# boden2021_V35.net
KiCad netlist of a schematic drawn in EAGLE
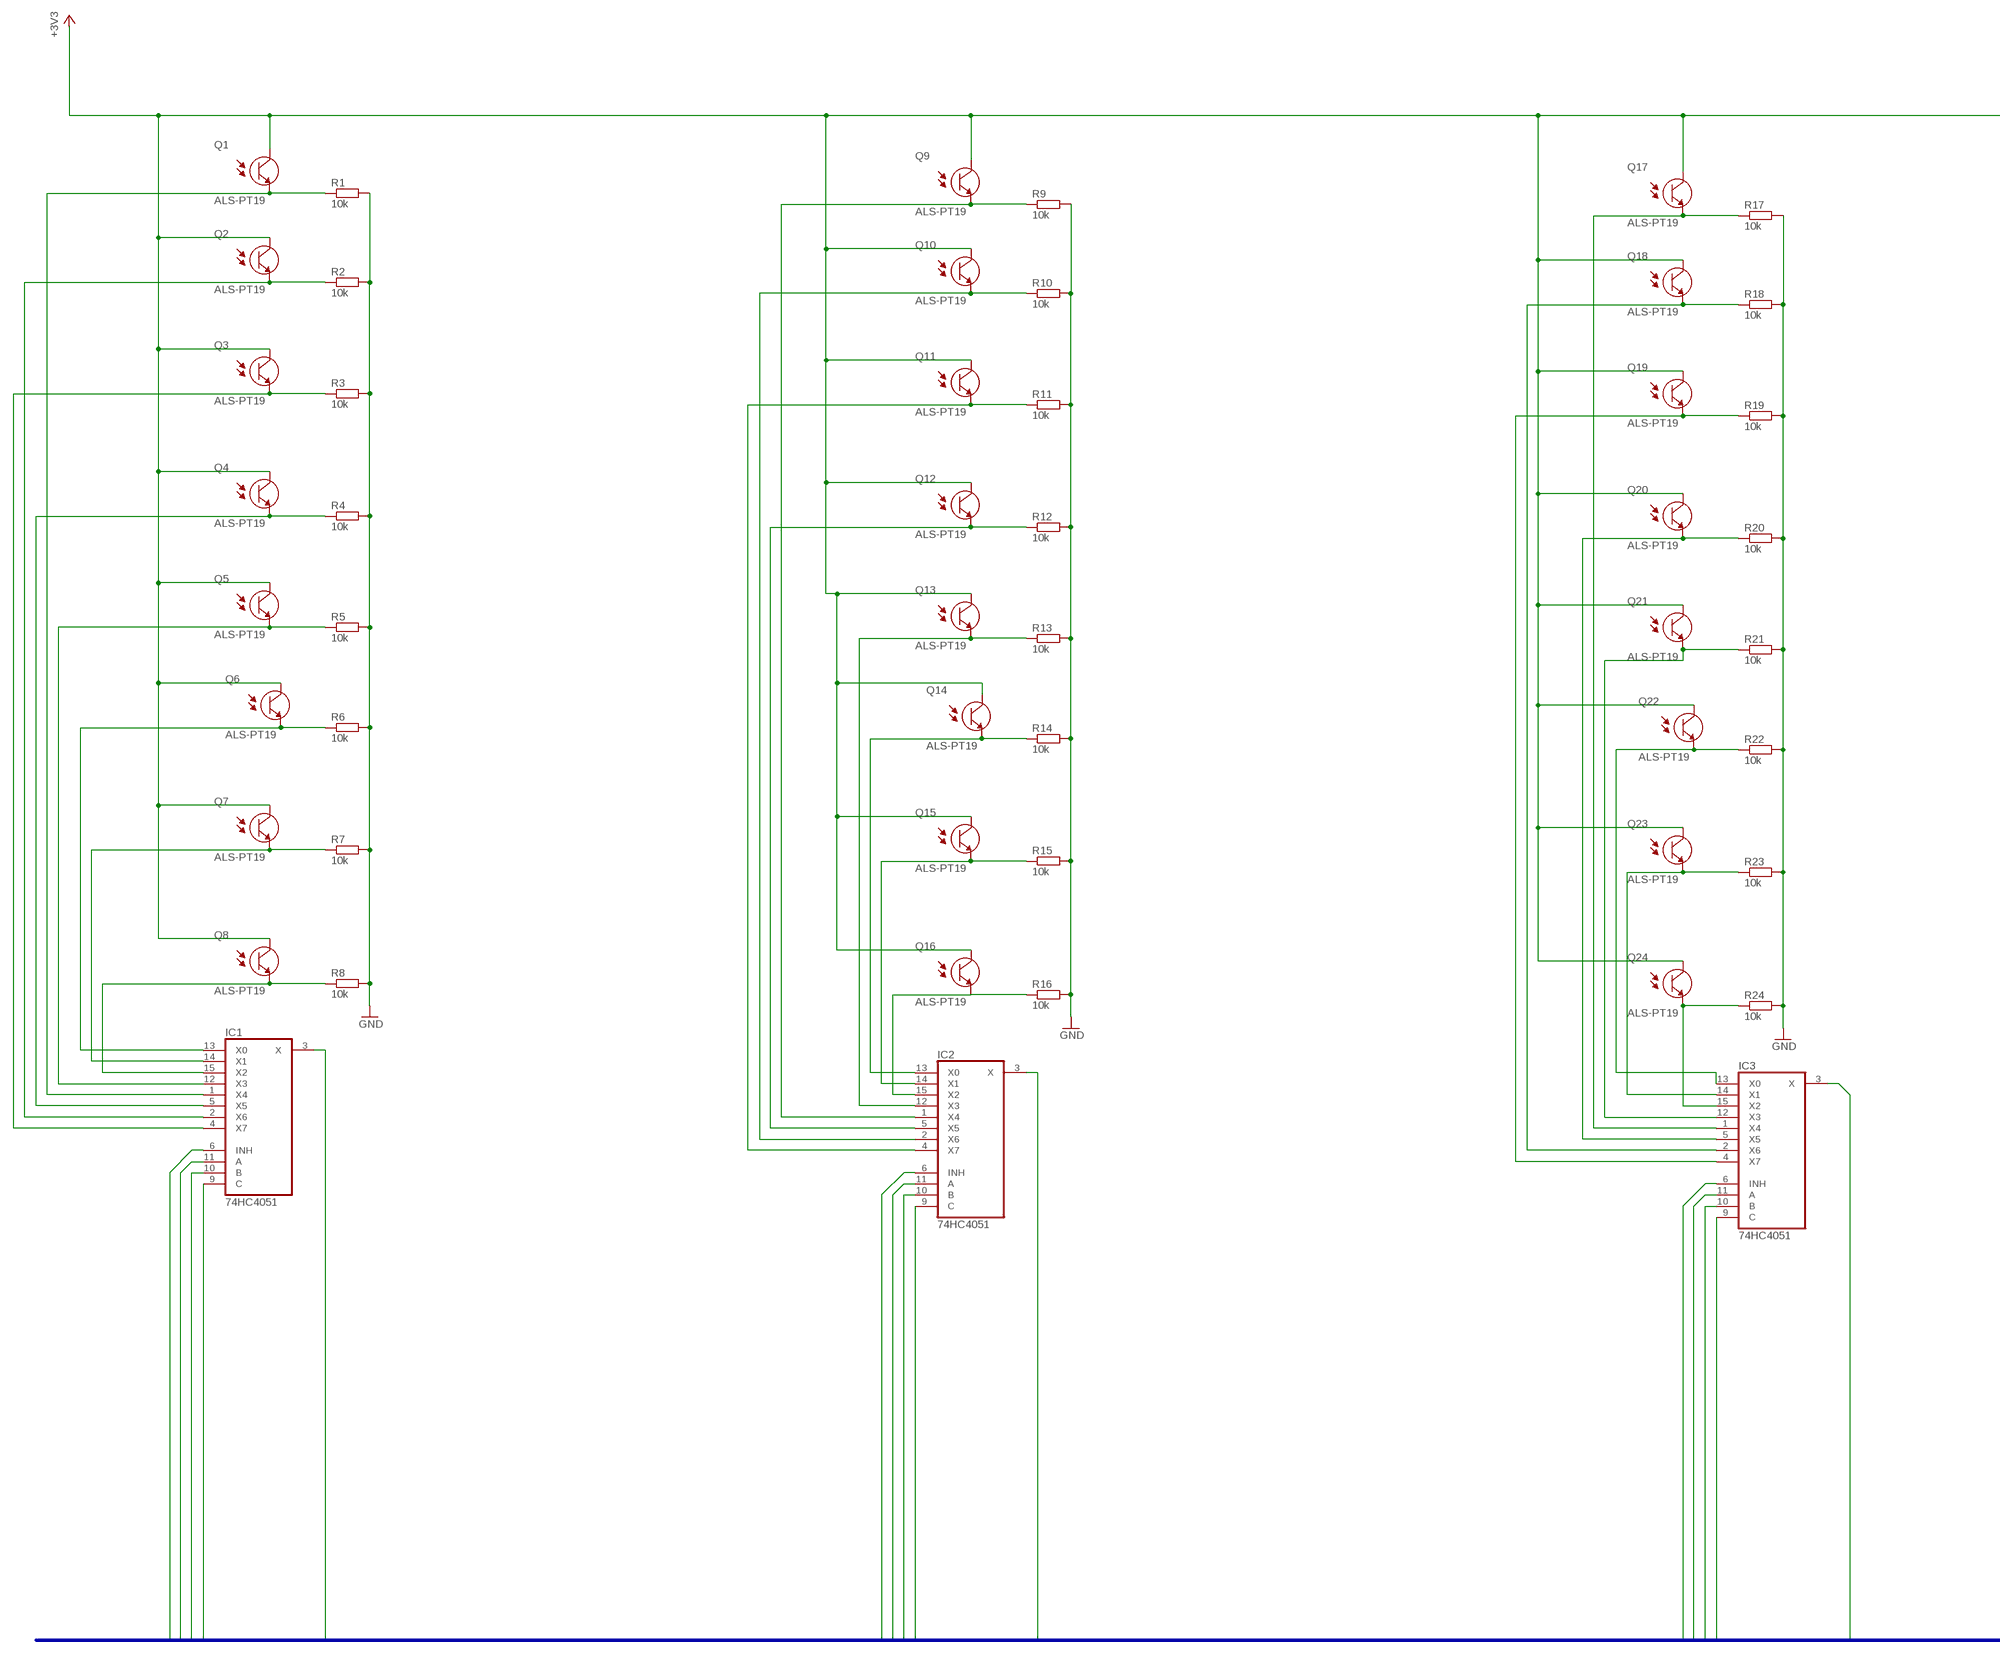
[diagram p0: schematic, sheet 1, part 1 of 3]
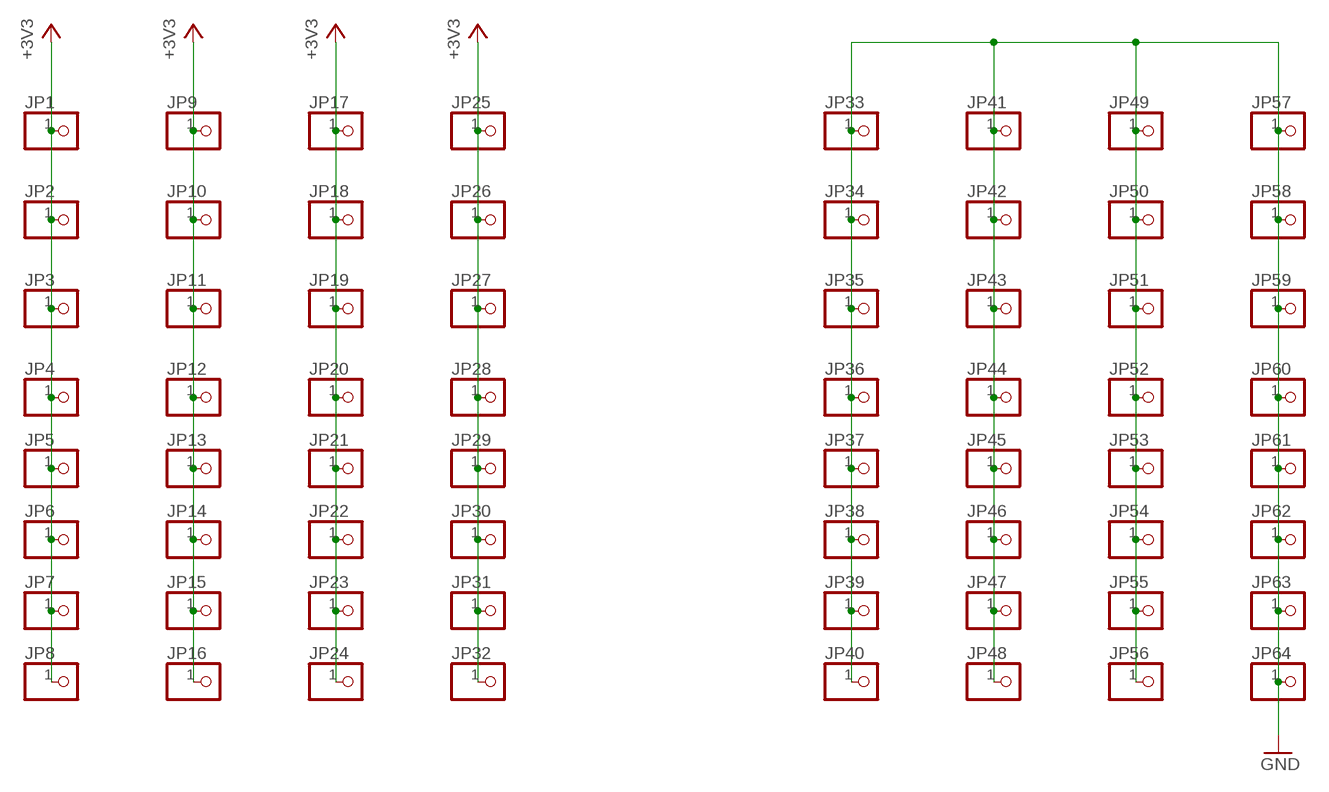
[diagram p1: schematic, sheet 1, part 2 of 3]
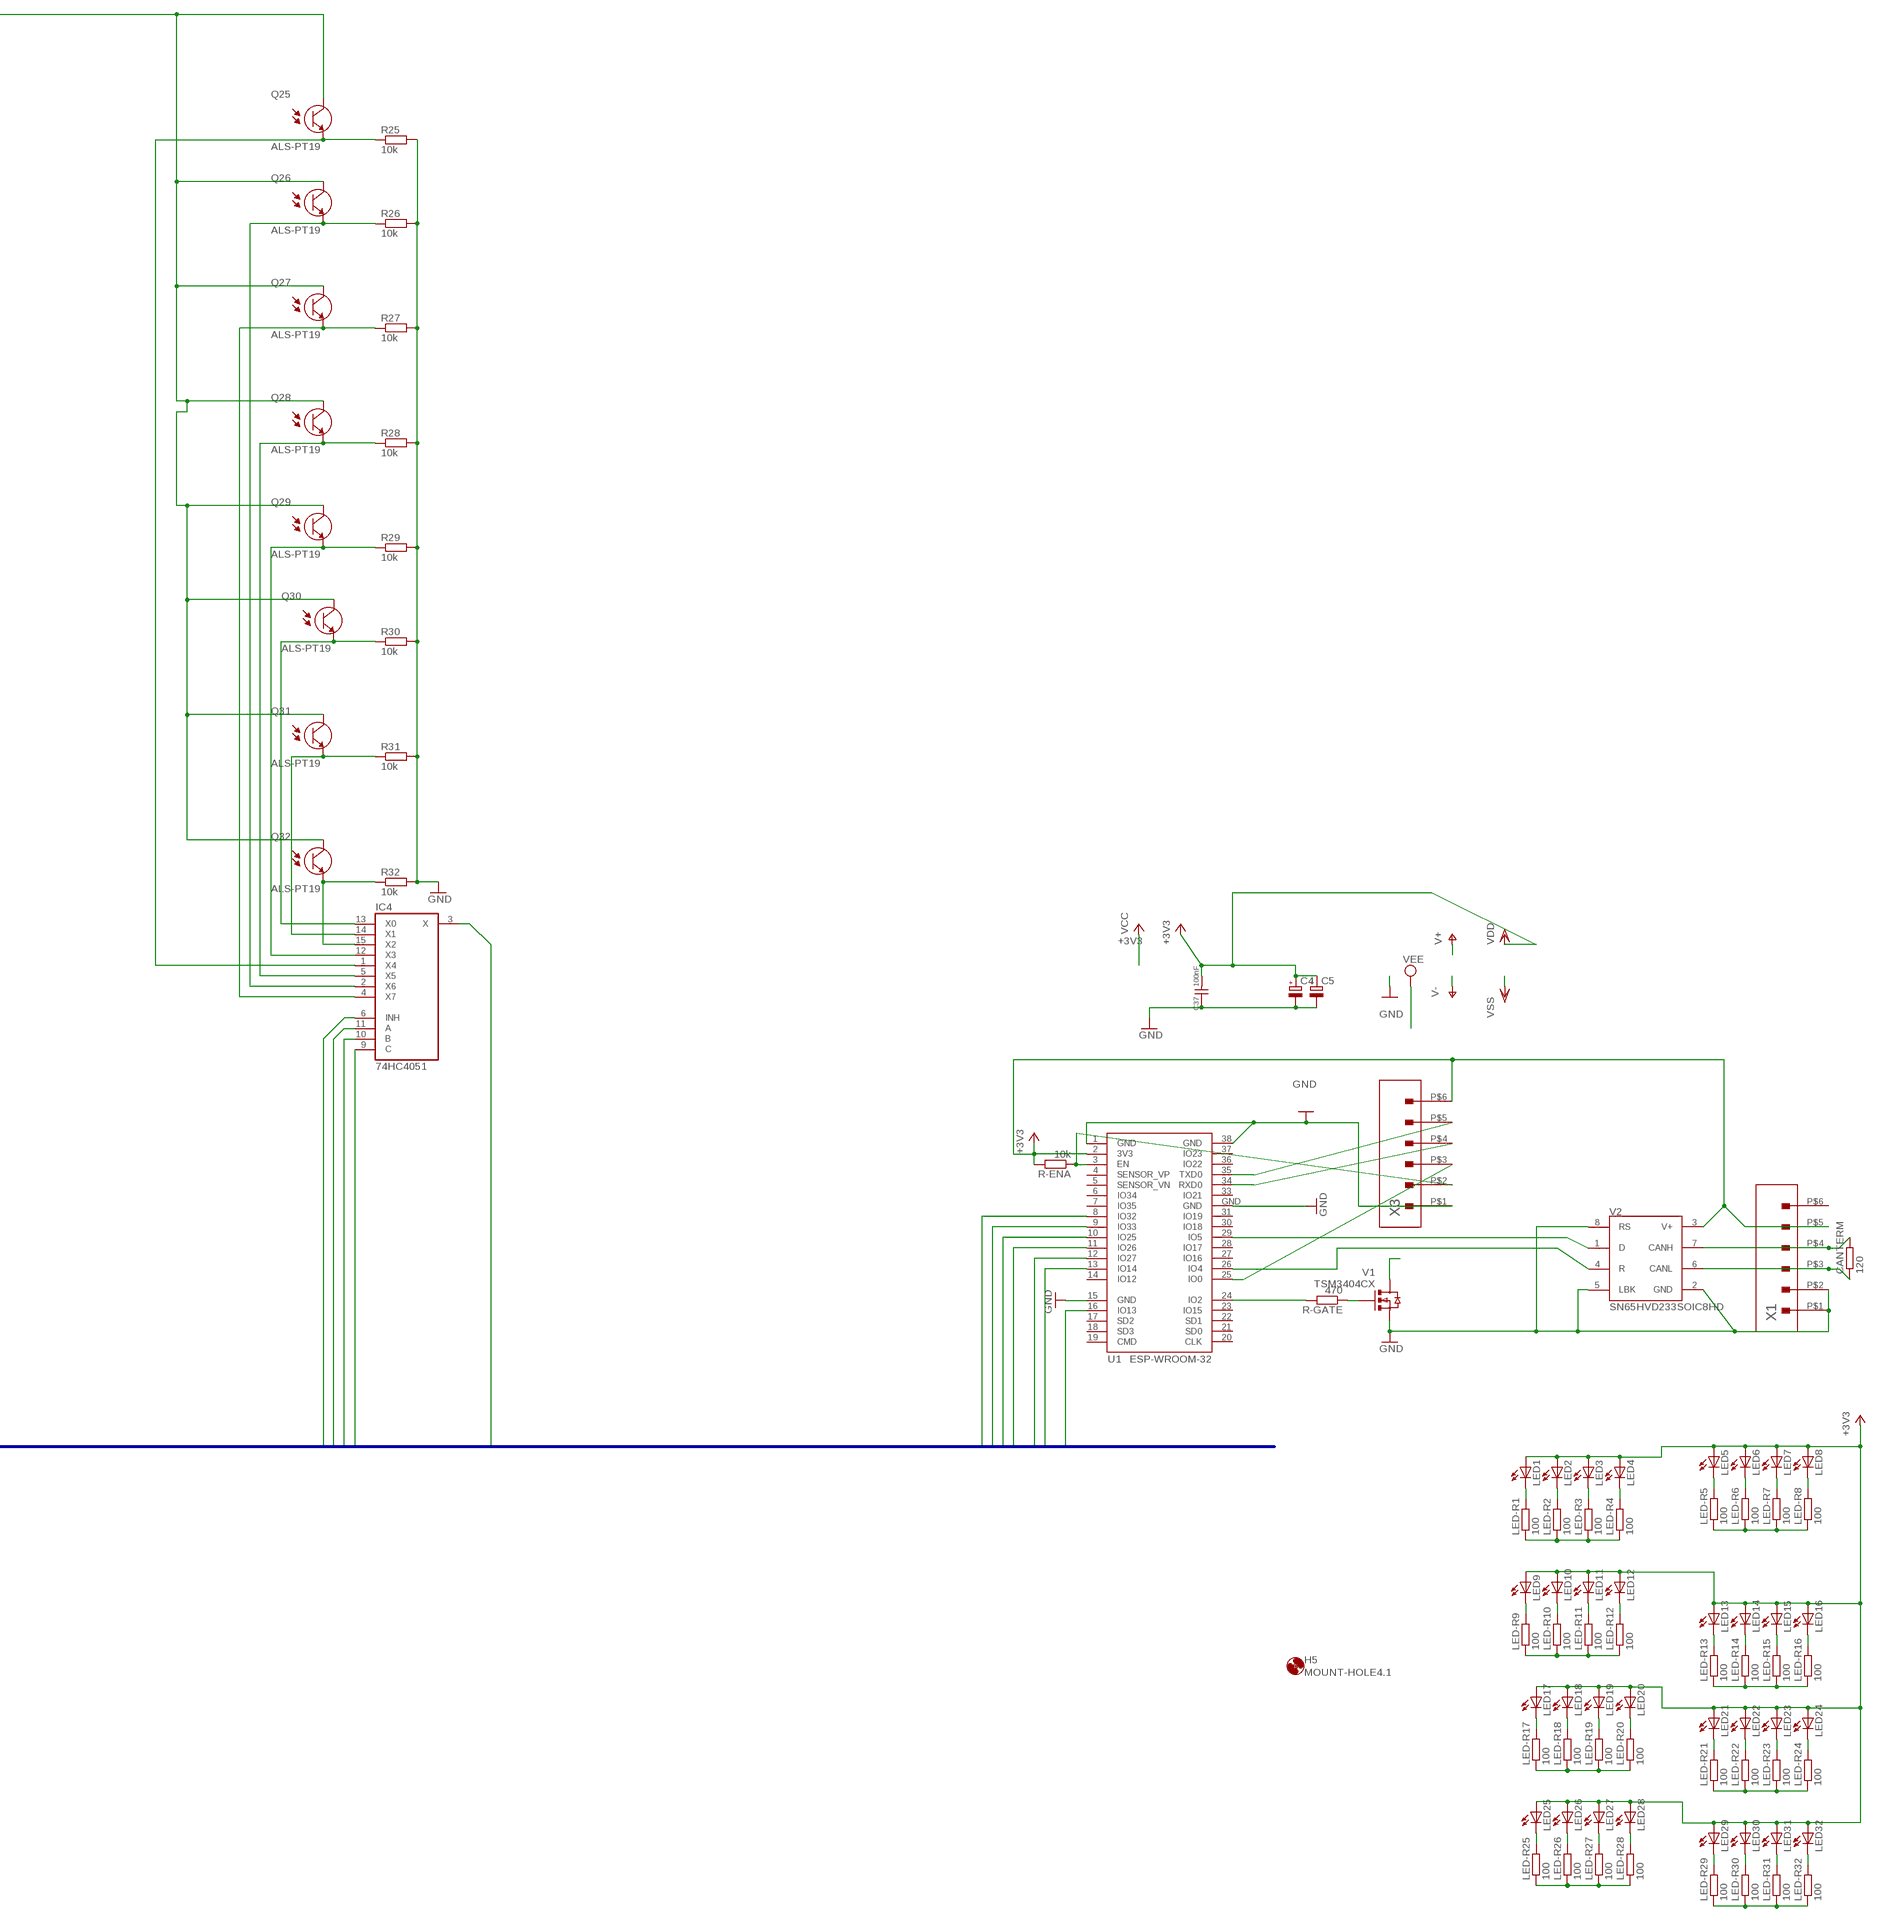
[diagram p2: schematic, sheet 1, part 3 of 3]

(export (version "E")
  (design (tool "Eeschema 10.0.6"))
  (components
    (comp (ref "C4")
      (value "CPOL-EUE2,5-6E")
      (footprint "eagle-import:E2,5-6E")
      (libsource (lib "eagle-import") (part "CPOL-EUE2,5-6E"))
    )
    (comp (ref "C5")
      (value "CPOL-EUE2,5-6E")
      (footprint "eagle-import:E2,5-6E")
      (libsource (lib "eagle-import") (part "CPOL-EUE2,5-6E"))
    )
    (comp (ref "C37")
      (value "100nF")
      (footprint "eagle-import:0805")
      (libsource (lib "eagle-import") (part "C0805"))
    )
    (comp (ref "CANTERM")
      (value "120")
      (footprint "eagle-import:R0603")
      (libsource (lib "eagle-import") (part "R-EU_R0603"))
    )
    (comp (ref "H5")
      (value "MOUNT-HOLE4.1")
      (footprint "eagle-import:4,1")
      (libsource (lib "eagle-import") (part "MOUNT-HOLE4.1"))
    )
    (comp (ref "IC1")
      (value "74HC4051")
      (footprint "eagle-import:TSSOP-16")
      (libsource (lib "eagle-import") (part "4051"))
    )
    (comp (ref "IC2")
      (value "74HC4051")
      (footprint "eagle-import:TSSOP-16")
      (libsource (lib "eagle-import") (part "4051"))
    )
    (comp (ref "IC3")
      (value "74HC4051")
      (footprint "eagle-import:TSSOP-16")
      (libsource (lib "eagle-import") (part "4051"))
    )
    (comp (ref "IC4")
      (value "74HC4051")
      (footprint "eagle-import:TSSOP-16")
      (libsource (lib "eagle-import") (part "4051"))
    )
    (comp (ref "JP1")
      (value "PINHD-1X1")
      (footprint "eagle-import:1X01")
      (libsource (lib "eagle-import") (part "PINHD-1X1"))
    )
    (comp (ref "JP2")
      (value "PINHD-1X1")
      (footprint "eagle-import:1X01")
      (libsource (lib "eagle-import") (part "PINHD-1X1"))
    )
    (comp (ref "JP3")
      (value "PINHD-1X1")
      (footprint "eagle-import:1X01")
      (libsource (lib "eagle-import") (part "PINHD-1X1"))
    )
    (comp (ref "JP4")
      (value "PINHD-1X1")
      (footprint "eagle-import:1X01")
      (libsource (lib "eagle-import") (part "PINHD-1X1"))
    )
    (comp (ref "JP5")
      (value "PINHD-1X1")
      (footprint "eagle-import:1X01")
      (libsource (lib "eagle-import") (part "PINHD-1X1"))
    )
    (comp (ref "JP6")
      (value "PINHD-1X1")
      (footprint "eagle-import:1X01")
      (libsource (lib "eagle-import") (part "PINHD-1X1"))
    )
    (comp (ref "JP7")
      (value "PINHD-1X1")
      (footprint "eagle-import:1X01")
      (libsource (lib "eagle-import") (part "PINHD-1X1"))
    )
    (comp (ref "JP8")
      (value "PINHD-1X1")
      (footprint "eagle-import:1X01")
      (libsource (lib "eagle-import") (part "PINHD-1X1"))
    )
    (comp (ref "JP9")
      (value "PINHD-1X1")
      (footprint "eagle-import:1X01")
      (libsource (lib "eagle-import") (part "PINHD-1X1"))
    )
    (comp (ref "JP10")
      (value "PINHD-1X1")
      (footprint "eagle-import:1X01")
      (libsource (lib "eagle-import") (part "PINHD-1X1"))
    )
    (comp (ref "JP11")
      (value "PINHD-1X1")
      (footprint "eagle-import:1X01")
      (libsource (lib "eagle-import") (part "PINHD-1X1"))
    )
    (comp (ref "JP12")
      (value "PINHD-1X1")
      (footprint "eagle-import:1X01")
      (libsource (lib "eagle-import") (part "PINHD-1X1"))
    )
    (comp (ref "JP13")
      (value "PINHD-1X1")
      (footprint "eagle-import:1X01")
      (libsource (lib "eagle-import") (part "PINHD-1X1"))
    )
    (comp (ref "JP14")
      (value "PINHD-1X1")
      (footprint "eagle-import:1X01")
      (libsource (lib "eagle-import") (part "PINHD-1X1"))
    )
    (comp (ref "JP15")
      (value "PINHD-1X1")
      (footprint "eagle-import:1X01")
      (libsource (lib "eagle-import") (part "PINHD-1X1"))
    )
    (comp (ref "JP16")
      (value "PINHD-1X1")
      (footprint "eagle-import:1X01")
      (libsource (lib "eagle-import") (part "PINHD-1X1"))
    )
    (comp (ref "JP17")
      (value "PINHD-1X1")
      (footprint "eagle-import:1X01")
      (libsource (lib "eagle-import") (part "PINHD-1X1"))
    )
    (comp (ref "JP18")
      (value "PINHD-1X1")
      (footprint "eagle-import:1X01")
      (libsource (lib "eagle-import") (part "PINHD-1X1"))
    )
    (comp (ref "JP19")
      (value "PINHD-1X1")
      (footprint "eagle-import:1X01")
      (libsource (lib "eagle-import") (part "PINHD-1X1"))
    )
    (comp (ref "JP20")
      (value "PINHD-1X1")
      (footprint "eagle-import:1X01")
      (libsource (lib "eagle-import") (part "PINHD-1X1"))
    )
    (comp (ref "JP21")
      (value "PINHD-1X1")
      (footprint "eagle-import:1X01")
      (libsource (lib "eagle-import") (part "PINHD-1X1"))
    )
    (comp (ref "JP22")
      (value "PINHD-1X1")
      (footprint "eagle-import:1X01")
      (libsource (lib "eagle-import") (part "PINHD-1X1"))
    )
    (comp (ref "JP23")
      (value "PINHD-1X1")
      (footprint "eagle-import:1X01")
      (libsource (lib "eagle-import") (part "PINHD-1X1"))
    )
    (comp (ref "JP24")
      (value "PINHD-1X1")
      (footprint "eagle-import:1X01")
      (libsource (lib "eagle-import") (part "PINHD-1X1"))
    )
    (comp (ref "JP25")
      (value "PINHD-1X1")
      (footprint "eagle-import:1X01")
      (libsource (lib "eagle-import") (part "PINHD-1X1"))
    )
    (comp (ref "JP26")
      (value "PINHD-1X1")
      (footprint "eagle-import:1X01")
      (libsource (lib "eagle-import") (part "PINHD-1X1"))
    )
    (comp (ref "JP27")
      (value "PINHD-1X1")
      (footprint "eagle-import:1X01")
      (libsource (lib "eagle-import") (part "PINHD-1X1"))
    )
    (comp (ref "JP28")
      (value "PINHD-1X1")
      (footprint "eagle-import:1X01")
      (libsource (lib "eagle-import") (part "PINHD-1X1"))
    )
    (comp (ref "JP29")
      (value "PINHD-1X1")
      (footprint "eagle-import:1X01")
      (libsource (lib "eagle-import") (part "PINHD-1X1"))
    )
    (comp (ref "JP30")
      (value "PINHD-1X1")
      (footprint "eagle-import:1X01")
      (libsource (lib "eagle-import") (part "PINHD-1X1"))
    )
    (comp (ref "JP31")
      (value "PINHD-1X1")
      (footprint "eagle-import:1X01")
      (libsource (lib "eagle-import") (part "PINHD-1X1"))
    )
    (comp (ref "JP32")
      (value "PINHD-1X1")
      (footprint "eagle-import:1X01")
      (libsource (lib "eagle-import") (part "PINHD-1X1"))
    )
    (comp (ref "JP33")
      (value "PINHD-1X1")
      (footprint "eagle-import:1X01")
      (libsource (lib "eagle-import") (part "PINHD-1X1"))
    )
    (comp (ref "JP34")
      (value "PINHD-1X1")
      (footprint "eagle-import:1X01")
      (libsource (lib "eagle-import") (part "PINHD-1X1"))
    )
    (comp (ref "JP35")
      (value "PINHD-1X1")
      (footprint "eagle-import:1X01")
      (libsource (lib "eagle-import") (part "PINHD-1X1"))
    )
    (comp (ref "JP36")
      (value "PINHD-1X1")
      (footprint "eagle-import:1X01")
      (libsource (lib "eagle-import") (part "PINHD-1X1"))
    )
    (comp (ref "JP37")
      (value "PINHD-1X1")
      (footprint "eagle-import:1X01")
      (libsource (lib "eagle-import") (part "PINHD-1X1"))
    )
    (comp (ref "JP38")
      (value "PINHD-1X1")
      (footprint "eagle-import:1X01")
      (libsource (lib "eagle-import") (part "PINHD-1X1"))
    )
    (comp (ref "JP39")
      (value "PINHD-1X1")
      (footprint "eagle-import:1X01")
      (libsource (lib "eagle-import") (part "PINHD-1X1"))
    )
    (comp (ref "JP40")
      (value "PINHD-1X1")
      (footprint "eagle-import:1X01")
      (libsource (lib "eagle-import") (part "PINHD-1X1"))
    )
    (comp (ref "JP41")
      (value "PINHD-1X1")
      (footprint "eagle-import:1X01")
      (libsource (lib "eagle-import") (part "PINHD-1X1"))
    )
    (comp (ref "JP42")
      (value "PINHD-1X1")
      (footprint "eagle-import:1X01")
      (libsource (lib "eagle-import") (part "PINHD-1X1"))
    )
    (comp (ref "JP43")
      (value "PINHD-1X1")
      (footprint "eagle-import:1X01")
      (libsource (lib "eagle-import") (part "PINHD-1X1"))
    )
    (comp (ref "JP44")
      (value "PINHD-1X1")
      (footprint "eagle-import:1X01")
      (libsource (lib "eagle-import") (part "PINHD-1X1"))
    )
    (comp (ref "JP45")
      (value "PINHD-1X1")
      (footprint "eagle-import:1X01")
      (libsource (lib "eagle-import") (part "PINHD-1X1"))
    )
    (comp (ref "JP46")
      (value "PINHD-1X1")
      (footprint "eagle-import:1X01")
      (libsource (lib "eagle-import") (part "PINHD-1X1"))
    )
    (comp (ref "JP47")
      (value "PINHD-1X1")
      (footprint "eagle-import:1X01")
      (libsource (lib "eagle-import") (part "PINHD-1X1"))
    )
    (comp (ref "JP48")
      (value "PINHD-1X1")
      (footprint "eagle-import:1X01")
      (libsource (lib "eagle-import") (part "PINHD-1X1"))
    )
    (comp (ref "JP49")
      (value "PINHD-1X1")
      (footprint "eagle-import:1X01")
      (libsource (lib "eagle-import") (part "PINHD-1X1"))
    )
    (comp (ref "JP50")
      (value "PINHD-1X1")
      (footprint "eagle-import:1X01")
      (libsource (lib "eagle-import") (part "PINHD-1X1"))
    )
    (comp (ref "JP51")
      (value "PINHD-1X1")
      (footprint "eagle-import:1X01")
      (libsource (lib "eagle-import") (part "PINHD-1X1"))
    )
    (comp (ref "JP52")
      (value "PINHD-1X1")
      (footprint "eagle-import:1X01")
      (libsource (lib "eagle-import") (part "PINHD-1X1"))
    )
    (comp (ref "JP53")
      (value "PINHD-1X1")
      (footprint "eagle-import:1X01")
      (libsource (lib "eagle-import") (part "PINHD-1X1"))
    )
    (comp (ref "JP54")
      (value "PINHD-1X1")
      (footprint "eagle-import:1X01")
      (libsource (lib "eagle-import") (part "PINHD-1X1"))
    )
    (comp (ref "JP55")
      (value "PINHD-1X1")
      (footprint "eagle-import:1X01")
      (libsource (lib "eagle-import") (part "PINHD-1X1"))
    )
    (comp (ref "JP56")
      (value "PINHD-1X1")
      (footprint "eagle-import:1X01")
      (libsource (lib "eagle-import") (part "PINHD-1X1"))
    )
    (comp (ref "JP57")
      (value "PINHD-1X1")
      (footprint "eagle-import:1X01")
      (libsource (lib "eagle-import") (part "PINHD-1X1"))
    )
    (comp (ref "JP58")
      (value "PINHD-1X1")
      (footprint "eagle-import:1X01")
      (libsource (lib "eagle-import") (part "PINHD-1X1"))
    )
    (comp (ref "JP59")
      (value "PINHD-1X1")
      (footprint "eagle-import:1X01")
      (libsource (lib "eagle-import") (part "PINHD-1X1"))
    )
    (comp (ref "JP60")
      (value "PINHD-1X1")
      (footprint "eagle-import:1X01")
      (libsource (lib "eagle-import") (part "PINHD-1X1"))
    )
    (comp (ref "JP61")
      (value "PINHD-1X1")
      (footprint "eagle-import:1X01")
      (libsource (lib "eagle-import") (part "PINHD-1X1"))
    )
    (comp (ref "JP62")
      (value "PINHD-1X1")
      (footprint "eagle-import:1X01")
      (libsource (lib "eagle-import") (part "PINHD-1X1"))
    )
    (comp (ref "JP63")
      (value "PINHD-1X1")
      (footprint "eagle-import:1X01")
      (libsource (lib "eagle-import") (part "PINHD-1X1"))
    )
    (comp (ref "JP64")
      (value "PINHD-1X1")
      (footprint "eagle-import:1X01")
      (libsource (lib "eagle-import") (part "PINHD-1X1"))
    )
    (comp (ref "LED-R1")
      (value "100")
      (footprint "eagle-import:R0805")
      (libsource (lib "eagle-import") (part "R-EU_R0805"))
    )
    (comp (ref "LED-R2")
      (value "100")
      (footprint "eagle-import:R0805")
      (libsource (lib "eagle-import") (part "R-EU_R0805"))
    )
    (comp (ref "LED-R3")
      (value "100")
      (footprint "eagle-import:R0805")
      (libsource (lib "eagle-import") (part "R-EU_R0805"))
    )
    (comp (ref "LED-R4")
      (value "100")
      (footprint "eagle-import:R0805")
      (libsource (lib "eagle-import") (part "R-EU_R0805"))
    )
    (comp (ref "LED-R5")
      (value "100")
      (footprint "eagle-import:R0805")
      (libsource (lib "eagle-import") (part "R-EU_R0805"))
    )
    (comp (ref "LED-R6")
      (value "100")
      (footprint "eagle-import:R0805")
      (libsource (lib "eagle-import") (part "R-EU_R0805"))
    )
    (comp (ref "LED-R7")
      (value "100")
      (footprint "eagle-import:R0805")
      (libsource (lib "eagle-import") (part "R-EU_R0805"))
    )
    (comp (ref "LED-R8")
      (value "100")
      (footprint "eagle-import:R0805")
      (libsource (lib "eagle-import") (part "R-EU_R0805"))
    )
    (comp (ref "LED-R9")
      (value "100")
      (footprint "eagle-import:R0805")
      (libsource (lib "eagle-import") (part "R-EU_R0805"))
    )
    (comp (ref "LED-R10")
      (value "100")
      (footprint "eagle-import:R0805")
      (libsource (lib "eagle-import") (part "R-EU_R0805"))
    )
    (comp (ref "LED-R11")
      (value "100")
      (footprint "eagle-import:R0805")
      (libsource (lib "eagle-import") (part "R-EU_R0805"))
    )
    (comp (ref "LED-R12")
      (value "100")
      (footprint "eagle-import:R0805")
      (libsource (lib "eagle-import") (part "R-EU_R0805"))
    )
    (comp (ref "LED-R13")
      (value "100")
      (footprint "eagle-import:R0805")
      (libsource (lib "eagle-import") (part "R-EU_R0805"))
    )
    (comp (ref "LED-R14")
      (value "100")
      (footprint "eagle-import:R0805")
      (libsource (lib "eagle-import") (part "R-EU_R0805"))
    )
    (comp (ref "LED-R15")
      (value "100")
      (footprint "eagle-import:R0805")
      (libsource (lib "eagle-import") (part "R-EU_R0805"))
    )
    (comp (ref "LED-R16")
      (value "100")
      (footprint "eagle-import:R0805")
      (libsource (lib "eagle-import") (part "R-EU_R0805"))
    )
    (comp (ref "LED-R17")
      (value "100")
      (footprint "eagle-import:R0805")
      (libsource (lib "eagle-import") (part "R-EU_R0805"))
    )
    (comp (ref "LED-R18")
      (value "100")
      (footprint "eagle-import:R0805")
      (libsource (lib "eagle-import") (part "R-EU_R0805"))
    )
    (comp (ref "LED-R19")
      (value "100")
      (footprint "eagle-import:R0805")
      (libsource (lib "eagle-import") (part "R-EU_R0805"))
    )
    (comp (ref "LED-R20")
      (value "100")
      (footprint "eagle-import:R0805")
      (libsource (lib "eagle-import") (part "R-EU_R0805"))
    )
    (comp (ref "LED-R21")
      (value "100")
      (footprint "eagle-import:R0805")
      (libsource (lib "eagle-import") (part "R-EU_R0805"))
    )
    (comp (ref "LED-R22")
      (value "100")
      (footprint "eagle-import:R0805")
      (libsource (lib "eagle-import") (part "R-EU_R0805"))
    )
    (comp (ref "LED-R23")
      (value "100")
      (footprint "eagle-import:R0805")
      (libsource (lib "eagle-import") (part "R-EU_R0805"))
    )
    (comp (ref "LED-R24")
      (value "100")
      (footprint "eagle-import:R0805")
      (libsource (lib "eagle-import") (part "R-EU_R0805"))
    )
    (comp (ref "LED-R25")
      (value "100")
      (footprint "eagle-import:R0805")
      (libsource (lib "eagle-import") (part "R-EU_R0805"))
    )
    (comp (ref "LED-R26")
      (value "100")
      (footprint "eagle-import:R0805")
      (libsource (lib "eagle-import") (part "R-EU_R0805"))
    )
    (comp (ref "LED-R27")
      (value "100")
      (footprint "eagle-import:R0805")
      (libsource (lib "eagle-import") (part "R-EU_R0805"))
    )
    (comp (ref "LED-R28")
      (value "100")
      (footprint "eagle-import:R0805")
      (libsource (lib "eagle-import") (part "R-EU_R0805"))
    )
    (comp (ref "LED-R29")
      (value "100")
      (footprint "eagle-import:R0805")
      (libsource (lib "eagle-import") (part "R-EU_R0805"))
    )
    (comp (ref "LED-R30")
      (value "100")
      (footprint "eagle-import:R0805")
      (libsource (lib "eagle-import") (part "R-EU_R0805"))
    )
    (comp (ref "LED-R31")
      (value "100")
      (footprint "eagle-import:R0805")
      (libsource (lib "eagle-import") (part "R-EU_R0805"))
    )
    (comp (ref "LED-R32")
      (value "100")
      (footprint "eagle-import:R0805")
      (libsource (lib "eagle-import") (part "R-EU_R0805"))
    )
    (comp (ref "LED1")
      (value "LEDP-LCC-2")
      (footprint "eagle-import:P-LCC-2")
      (libsource (lib "eagle-import") (part "LEDP-LCC-2"))
    )
    (comp (ref "LED2")
      (value "LEDP-LCC-2")
      (footprint "eagle-import:P-LCC-2")
      (libsource (lib "eagle-import") (part "LEDP-LCC-2"))
    )
    (comp (ref "LED3")
      (value "LEDP-LCC-2")
      (footprint "eagle-import:P-LCC-2")
      (libsource (lib "eagle-import") (part "LEDP-LCC-2"))
    )
    (comp (ref "LED4")
      (value "LEDP-LCC-2")
      (footprint "eagle-import:P-LCC-2")
      (libsource (lib "eagle-import") (part "LEDP-LCC-2"))
    )
    (comp (ref "LED5")
      (value "LEDP-LCC-2")
      (footprint "eagle-import:P-LCC-2")
      (libsource (lib "eagle-import") (part "LEDP-LCC-2"))
    )
    (comp (ref "LED6")
      (value "LEDP-LCC-2")
      (footprint "eagle-import:P-LCC-2")
      (libsource (lib "eagle-import") (part "LEDP-LCC-2"))
    )
    (comp (ref "LED7")
      (value "LEDP-LCC-2")
      (footprint "eagle-import:P-LCC-2")
      (libsource (lib "eagle-import") (part "LEDP-LCC-2"))
    )
    (comp (ref "LED8")
      (value "LEDP-LCC-2")
      (footprint "eagle-import:P-LCC-2")
      (libsource (lib "eagle-import") (part "LEDP-LCC-2"))
    )
    (comp (ref "LED9")
      (value "LEDP-LCC-2")
      (footprint "eagle-import:P-LCC-2")
      (libsource (lib "eagle-import") (part "LEDP-LCC-2"))
    )
    (comp (ref "LED10")
      (value "LEDP-LCC-2")
      (footprint "eagle-import:P-LCC-2")
      (libsource (lib "eagle-import") (part "LEDP-LCC-2"))
    )
    (comp (ref "LED11")
      (value "LEDP-LCC-2")
      (footprint "eagle-import:P-LCC-2")
      (libsource (lib "eagle-import") (part "LEDP-LCC-2"))
    )
    (comp (ref "LED12")
      (value "LEDP-LCC-2")
      (footprint "eagle-import:P-LCC-2")
      (libsource (lib "eagle-import") (part "LEDP-LCC-2"))
    )
    (comp (ref "LED13")
      (value "LEDP-LCC-2")
      (footprint "eagle-import:P-LCC-2")
      (libsource (lib "eagle-import") (part "LEDP-LCC-2"))
    )
    (comp (ref "LED14")
      (value "LEDP-LCC-2")
      (footprint "eagle-import:P-LCC-2")
      (libsource (lib "eagle-import") (part "LEDP-LCC-2"))
    )
    (comp (ref "LED15")
      (value "LEDP-LCC-2")
      (footprint "eagle-import:P-LCC-2")
      (libsource (lib "eagle-import") (part "LEDP-LCC-2"))
    )
    (comp (ref "LED16")
      (value "LEDP-LCC-2")
      (footprint "eagle-import:P-LCC-2")
      (libsource (lib "eagle-import") (part "LEDP-LCC-2"))
    )
    (comp (ref "LED17")
      (value "LEDP-LCC-2")
      (footprint "eagle-import:P-LCC-2")
      (libsource (lib "eagle-import") (part "LEDP-LCC-2"))
    )
    (comp (ref "LED18")
      (value "LEDP-LCC-2")
      (footprint "eagle-import:P-LCC-2")
      (libsource (lib "eagle-import") (part "LEDP-LCC-2"))
    )
    (comp (ref "LED19")
      (value "LEDP-LCC-2")
      (footprint "eagle-import:P-LCC-2")
      (libsource (lib "eagle-import") (part "LEDP-LCC-2"))
    )
    (comp (ref "LED20")
      (value "LEDP-LCC-2")
      (footprint "eagle-import:P-LCC-2")
      (libsource (lib "eagle-import") (part "LEDP-LCC-2"))
    )
    (comp (ref "LED21")
      (value "LEDP-LCC-2")
      (footprint "eagle-import:P-LCC-2")
      (libsource (lib "eagle-import") (part "LEDP-LCC-2"))
    )
    (comp (ref "LED22")
      (value "LEDP-LCC-2")
      (footprint "eagle-import:P-LCC-2")
      (libsource (lib "eagle-import") (part "LEDP-LCC-2"))
    )
    (comp (ref "LED23")
      (value "LEDP-LCC-2")
      (footprint "eagle-import:P-LCC-2")
      (libsource (lib "eagle-import") (part "LEDP-LCC-2"))
    )
    (comp (ref "LED24")
      (value "LEDP-LCC-2")
      (footprint "eagle-import:P-LCC-2")
      (libsource (lib "eagle-import") (part "LEDP-LCC-2"))
    )
    (comp (ref "LED25")
      (value "LEDP-LCC-2")
      (footprint "eagle-import:P-LCC-2")
      (libsource (lib "eagle-import") (part "LEDP-LCC-2"))
    )
    (comp (ref "LED26")
      (value "LEDP-LCC-2")
      (footprint "eagle-import:P-LCC-2")
      (libsource (lib "eagle-import") (part "LEDP-LCC-2"))
    )
    (comp (ref "LED27")
      (value "LEDP-LCC-2")
      (footprint "eagle-import:P-LCC-2")
      (libsource (lib "eagle-import") (part "LEDP-LCC-2"))
    )
    (comp (ref "LED28")
      (value "LEDP-LCC-2")
      (footprint "eagle-import:P-LCC-2")
      (libsource (lib "eagle-import") (part "LEDP-LCC-2"))
    )
    (comp (ref "LED29")
      (value "LEDP-LCC-2")
      (footprint "eagle-import:P-LCC-2")
      (libsource (lib "eagle-import") (part "LEDP-LCC-2"))
    )
    (comp (ref "LED30")
      (value "LEDP-LCC-2")
      (footprint "eagle-import:P-LCC-2")
      (libsource (lib "eagle-import") (part "LEDP-LCC-2"))
    )
    (comp (ref "LED31")
      (value "LEDP-LCC-2")
      (footprint "eagle-import:P-LCC-2")
      (libsource (lib "eagle-import") (part "LEDP-LCC-2"))
    )
    (comp (ref "LED32")
      (value "LEDP-LCC-2")
      (footprint "eagle-import:P-LCC-2")
      (libsource (lib "eagle-import") (part "LEDP-LCC-2"))
    )
    (comp (ref "Q1")
      (value "ALS-PT19")
      (footprint "eagle-import:ALSPT19315CL177TR8")
      (libsource (lib "eagle-import") (part "ALS-PT19"))
    )
    (comp (ref "Q2")
      (value "ALS-PT19")
      (footprint "eagle-import:ALSPT19315CL177TR8")
      (libsource (lib "eagle-import") (part "ALS-PT19"))
    )
    (comp (ref "Q3")
      (value "ALS-PT19")
      (footprint "eagle-import:ALSPT19315CL177TR8")
      (libsource (lib "eagle-import") (part "ALS-PT19"))
    )
    (comp (ref "Q4")
      (value "ALS-PT19")
      (footprint "eagle-import:ALSPT19315CL177TR8")
      (libsource (lib "eagle-import") (part "ALS-PT19"))
    )
    (comp (ref "Q5")
      (value "ALS-PT19")
      (footprint "eagle-import:ALSPT19315CL177TR8")
      (libsource (lib "eagle-import") (part "ALS-PT19"))
    )
    (comp (ref "Q6")
      (value "ALS-PT19")
      (footprint "eagle-import:ALSPT19315CL177TR8")
      (libsource (lib "eagle-import") (part "ALS-PT19"))
    )
    (comp (ref "Q7")
      (value "ALS-PT19")
      (footprint "eagle-import:ALSPT19315CL177TR8")
      (libsource (lib "eagle-import") (part "ALS-PT19"))
    )
    (comp (ref "Q8")
      (value "ALS-PT19")
      (footprint "eagle-import:ALSPT19315CL177TR8")
      (libsource (lib "eagle-import") (part "ALS-PT19"))
    )
    (comp (ref "Q9")
      (value "ALS-PT19")
      (footprint "eagle-import:ALSPT19315CL177TR8")
      (libsource (lib "eagle-import") (part "ALS-PT19"))
    )
    (comp (ref "Q10")
      (value "ALS-PT19")
      (footprint "eagle-import:ALSPT19315CL177TR8")
      (libsource (lib "eagle-import") (part "ALS-PT19"))
    )
    (comp (ref "Q11")
      (value "ALS-PT19")
      (footprint "eagle-import:ALSPT19315CL177TR8")
      (libsource (lib "eagle-import") (part "ALS-PT19"))
    )
    (comp (ref "Q12")
      (value "ALS-PT19")
      (footprint "eagle-import:ALSPT19315CL177TR8")
      (libsource (lib "eagle-import") (part "ALS-PT19"))
    )
    (comp (ref "Q13")
      (value "ALS-PT19")
      (footprint "eagle-import:ALSPT19315CL177TR8")
      (libsource (lib "eagle-import") (part "ALS-PT19"))
    )
    (comp (ref "Q14")
      (value "ALS-PT19")
      (footprint "eagle-import:ALSPT19315CL177TR8")
      (libsource (lib "eagle-import") (part "ALS-PT19"))
    )
    (comp (ref "Q15")
      (value "ALS-PT19")
      (footprint "eagle-import:ALSPT19315CL177TR8")
      (libsource (lib "eagle-import") (part "ALS-PT19"))
    )
    (comp (ref "Q16")
      (value "ALS-PT19")
      (footprint "eagle-import:ALSPT19315CL177TR8")
      (libsource (lib "eagle-import") (part "ALS-PT19"))
    )
    (comp (ref "Q17")
      (value "ALS-PT19")
      (footprint "eagle-import:ALSPT19315CL177TR8")
      (libsource (lib "eagle-import") (part "ALS-PT19"))
    )
    (comp (ref "Q18")
      (value "ALS-PT19")
      (footprint "eagle-import:ALSPT19315CL177TR8")
      (libsource (lib "eagle-import") (part "ALS-PT19"))
    )
    (comp (ref "Q19")
      (value "ALS-PT19")
      (footprint "eagle-import:ALSPT19315CL177TR8")
      (libsource (lib "eagle-import") (part "ALS-PT19"))
    )
    (comp (ref "Q20")
      (value "ALS-PT19")
      (footprint "eagle-import:ALSPT19315CL177TR8")
      (libsource (lib "eagle-import") (part "ALS-PT19"))
    )
    (comp (ref "Q21")
      (value "ALS-PT19")
      (footprint "eagle-import:ALSPT19315CL177TR8")
      (libsource (lib "eagle-import") (part "ALS-PT19"))
    )
    (comp (ref "Q22")
      (value "ALS-PT19")
      (footprint "eagle-import:ALSPT19315CL177TR8")
      (libsource (lib "eagle-import") (part "ALS-PT19"))
    )
    (comp (ref "Q23")
      (value "ALS-PT19")
      (footprint "eagle-import:ALSPT19315CL177TR8")
      (libsource (lib "eagle-import") (part "ALS-PT19"))
    )
    (comp (ref "Q24")
      (value "ALS-PT19")
      (footprint "eagle-import:ALSPT19315CL177TR8")
      (libsource (lib "eagle-import") (part "ALS-PT19"))
    )
    (comp (ref "Q25")
      (value "ALS-PT19")
      (footprint "eagle-import:ALSPT19315CL177TR8")
      (libsource (lib "eagle-import") (part "ALS-PT19"))
    )
    (comp (ref "Q26")
      (value "ALS-PT19")
      (footprint "eagle-import:ALSPT19315CL177TR8")
      (libsource (lib "eagle-import") (part "ALS-PT19"))
    )
    (comp (ref "Q27")
      (value "ALS-PT19")
      (footprint "eagle-import:ALSPT19315CL177TR8")
      (libsource (lib "eagle-import") (part "ALS-PT19"))
    )
    (comp (ref "Q28")
      (value "ALS-PT19")
      (footprint "eagle-import:ALSPT19315CL177TR8")
      (libsource (lib "eagle-import") (part "ALS-PT19"))
    )
    (comp (ref "Q29")
      (value "ALS-PT19")
      (footprint "eagle-import:ALSPT19315CL177TR8")
      (libsource (lib "eagle-import") (part "ALS-PT19"))
    )
    (comp (ref "Q30")
      (value "ALS-PT19")
      (footprint "eagle-import:ALSPT19315CL177TR8")
      (libsource (lib "eagle-import") (part "ALS-PT19"))
    )
    (comp (ref "Q31")
      (value "ALS-PT19")
      (footprint "eagle-import:ALSPT19315CL177TR8")
      (libsource (lib "eagle-import") (part "ALS-PT19"))
    )
    (comp (ref "Q32")
      (value "ALS-PT19")
      (footprint "eagle-import:ALSPT19315CL177TR8")
      (libsource (lib "eagle-import") (part "ALS-PT19"))
    )
    (comp (ref "R-ENA")
      (value "10k")
      (footprint "eagle-import:R0603")
      (libsource (lib "eagle-import") (part "rcl@1_R-EU_R0603"))
    )
    (comp (ref "R-GATE")
      (value "470")
      (footprint "eagle-import:R0603")
      (libsource (lib "eagle-import") (part "rcl_334_R-EU_R0603"))
    )
    (comp (ref "R1")
      (value "10k")
      (footprint "eagle-import:R0603")
      (libsource (lib "eagle-import") (part "rcl_334_R-EU_R0603"))
    )
    (comp (ref "R2")
      (value "10k")
      (footprint "eagle-import:R0603")
      (libsource (lib "eagle-import") (part "rcl_334_R-EU_R0603"))
    )
    (comp (ref "R3")
      (value "10k")
      (footprint "eagle-import:R0603")
      (libsource (lib "eagle-import") (part "rcl_334_R-EU_R0603"))
    )
    (comp (ref "R4")
      (value "10k")
      (footprint "eagle-import:R0603")
      (libsource (lib "eagle-import") (part "rcl_334_R-EU_R0603"))
    )
    (comp (ref "R5")
      (value "10k")
      (footprint "eagle-import:R0603")
      (libsource (lib "eagle-import") (part "rcl_334_R-EU_R0603"))
    )
    (comp (ref "R6")
      (value "10k")
      (footprint "eagle-import:R0603")
      (libsource (lib "eagle-import") (part "rcl_334_R-EU_R0603"))
    )
    (comp (ref "R7")
      (value "10k")
      (footprint "eagle-import:R0603")
      (libsource (lib "eagle-import") (part "rcl_334_R-EU_R0603"))
    )
    (comp (ref "R8")
      (value "10k")
      (footprint "eagle-import:R0603")
      (libsource (lib "eagle-import") (part "rcl_334_R-EU_R0603"))
    )
    (comp (ref "R9")
      (value "10k")
      (footprint "eagle-import:R0603")
      (libsource (lib "eagle-import") (part "rcl_334_R-EU_R0603"))
    )
    (comp (ref "R10")
      (value "10k")
      (footprint "eagle-import:R0603")
      (libsource (lib "eagle-import") (part "rcl_334_R-EU_R0603"))
    )
    (comp (ref "R11")
      (value "10k")
      (footprint "eagle-import:R0603")
      (libsource (lib "eagle-import") (part "rcl_334_R-EU_R0603"))
    )
    (comp (ref "R12")
      (value "10k")
      (footprint "eagle-import:R0603")
      (libsource (lib "eagle-import") (part "rcl_334_R-EU_R0603"))
    )
    (comp (ref "R13")
      (value "10k")
      (footprint "eagle-import:R0603")
      (libsource (lib "eagle-import") (part "rcl_334_R-EU_R0603"))
    )
    (comp (ref "R14")
      (value "10k")
      (footprint "eagle-import:R0603")
      (libsource (lib "eagle-import") (part "rcl_334_R-EU_R0603"))
    )
    (comp (ref "R15")
      (value "10k")
      (footprint "eagle-import:R0603")
      (libsource (lib "eagle-import") (part "rcl_334_R-EU_R0603"))
    )
    (comp (ref "R16")
      (value "10k")
      (footprint "eagle-import:R0603")
      (libsource (lib "eagle-import") (part "rcl_334_R-EU_R0603"))
    )
    (comp (ref "R17")
      (value "10k")
      (footprint "eagle-import:R0603")
      (libsource (lib "eagle-import") (part "rcl_334_R-EU_R0603"))
    )
    (comp (ref "R18")
      (value "10k")
      (footprint "eagle-import:R0603")
      (libsource (lib "eagle-import") (part "rcl_334_R-EU_R0603"))
    )
    (comp (ref "R19")
      (value "10k")
      (footprint "eagle-import:R0603")
      (libsource (lib "eagle-import") (part "rcl_334_R-EU_R0603"))
    )
    (comp (ref "R20")
      (value "10k")
      (footprint "eagle-import:R0603")
      (libsource (lib "eagle-import") (part "rcl_334_R-EU_R0603"))
    )
    (comp (ref "R21")
      (value "10k")
      (footprint "eagle-import:R0603")
      (libsource (lib "eagle-import") (part "rcl_334_R-EU_R0603"))
    )
    (comp (ref "R22")
      (value "10k")
      (footprint "eagle-import:R0603")
      (libsource (lib "eagle-import") (part "rcl_334_R-EU_R0603"))
    )
    (comp (ref "R23")
      (value "10k")
      (footprint "eagle-import:R0603")
      (libsource (lib "eagle-import") (part "rcl_334_R-EU_R0603"))
    )
    (comp (ref "R24")
      (value "10k")
      (footprint "eagle-import:R0603")
      (libsource (lib "eagle-import") (part "rcl_334_R-EU_R0603"))
    )
    (comp (ref "R25")
      (value "10k")
      (footprint "eagle-import:R0603")
      (libsource (lib "eagle-import") (part "rcl_334_R-EU_R0603"))
    )
    (comp (ref "R26")
      (value "10k")
      (footprint "eagle-import:R0603")
      (libsource (lib "eagle-import") (part "rcl_334_R-EU_R0603"))
    )
    (comp (ref "R27")
      (value "10k")
      (footprint "eagle-import:R0603")
      (libsource (lib "eagle-import") (part "rcl_334_R-EU_R0603"))
    )
    (comp (ref "R28")
      (value "10k")
      (footprint "eagle-import:R0603")
      (libsource (lib "eagle-import") (part "rcl_334_R-EU_R0603"))
    )
    (comp (ref "R29")
      (value "10k")
      (footprint "eagle-import:R0603")
      (libsource (lib "eagle-import") (part "rcl_334_R-EU_R0603"))
    )
    (comp (ref "R30")
      (value "10k")
      (footprint "eagle-import:R0603")
      (libsource (lib "eagle-import") (part "rcl_334_R-EU_R0603"))
    )
    (comp (ref "R31")
      (value "10k")
      (footprint "eagle-import:R0603")
      (libsource (lib "eagle-import") (part "rcl_334_R-EU_R0603"))
    )
    (comp (ref "R32")
      (value "10k")
      (footprint "eagle-import:R0603")
      (libsource (lib "eagle-import") (part "rcl_334_R-EU_R0603"))
    )
    (comp (ref "U1")
      (value "ESP-WROOM-32")
      (footprint "eagle-import:ESP-WROOM-32")
      (libsource (lib "eagle-import") (part "ESP-WROOM-32"))
    )
    (comp (ref "V1")
      (value "TSM3404CX")
      (footprint "eagle-import:SOT23")
      (libsource (lib "eagle-import") (part "TSM3404CX"))
    )
    (comp (ref "V2")
      (value "SN65HVD233SOIC8HD")
      (footprint "eagle-import:SO08")
      (libsource (lib "eagle-import") (part "SN65HVD233HDSOIC8"))
    )
    (comp (ref "X1")
      (value "MOLEX104078-0610")
      (footprint "eagle-import:MOLEX104078-0610")
      (libsource (lib "eagle-import") (part "MOLEX104078-0610"))
    )
    (comp (ref "X3")
      (value "MOLEX104078-0610")
      (footprint "eagle-import:MOLEX104078-0610")
      (libsource (lib "eagle-import") (part "MOLEX104078-0610"))
    )
  )
  (nets
    (net (code "1") (name "+3V3") (class "Default")
      (node (ref "C37") (pin "1") (pinfunction "1_1") (pintype "passive"))
      (node (ref "C4") (pin "+") (pinfunction "+_+") (pintype "passive"))
      (node (ref "C5") (pin "+") (pinfunction "+_+") (pintype "passive"))
      (node (ref "JP1") (pin "1") (pinfunction "1_1") (pintype "passive"))
      (node (ref "JP10") (pin "1") (pinfunction "1_1") (pintype "passive"))
      (node (ref "JP11") (pin "1") (pinfunction "1_1") (pintype "passive"))
      (node (ref "JP12") (pin "1") (pinfunction "1_1") (pintype "passive"))
      (node (ref "JP13") (pin "1") (pinfunction "1_1") (pintype "passive"))
      (node (ref "JP14") (pin "1") (pinfunction "1_1") (pintype "passive"))
      (node (ref "JP15") (pin "1") (pinfunction "1_1") (pintype "passive"))
      (node (ref "JP16") (pin "1") (pinfunction "1_1") (pintype "passive"))
      (node (ref "JP17") (pin "1") (pinfunction "1_1") (pintype "passive"))
      (node (ref "JP18") (pin "1") (pinfunction "1_1") (pintype "passive"))
      (node (ref "JP19") (pin "1") (pinfunction "1_1") (pintype "passive"))
      (node (ref "JP2") (pin "1") (pinfunction "1_1") (pintype "passive"))
      (node (ref "JP20") (pin "1") (pinfunction "1_1") (pintype "passive"))
      (node (ref "JP21") (pin "1") (pinfunction "1_1") (pintype "passive"))
      (node (ref "JP22") (pin "1") (pinfunction "1_1") (pintype "passive"))
      (node (ref "JP23") (pin "1") (pinfunction "1_1") (pintype "passive"))
      (node (ref "JP24") (pin "1") (pinfunction "1_1") (pintype "passive"))
      (node (ref "JP25") (pin "1") (pinfunction "1_1") (pintype "passive"))
      (node (ref "JP26") (pin "1") (pinfunction "1_1") (pintype "passive"))
      (node (ref "JP27") (pin "1") (pinfunction "1_1") (pintype "passive"))
      (node (ref "JP28") (pin "1") (pinfunction "1_1") (pintype "passive"))
      (node (ref "JP29") (pin "1") (pinfunction "1_1") (pintype "passive"))
      (node (ref "JP3") (pin "1") (pinfunction "1_1") (pintype "passive"))
      (node (ref "JP30") (pin "1") (pinfunction "1_1") (pintype "passive"))
      (node (ref "JP31") (pin "1") (pinfunction "1_1") (pintype "passive"))
      (node (ref "JP32") (pin "1") (pinfunction "1_1") (pintype "passive"))
      (node (ref "JP4") (pin "1") (pinfunction "1_1") (pintype "passive"))
      (node (ref "JP5") (pin "1") (pinfunction "1_1") (pintype "passive"))
      (node (ref "JP6") (pin "1") (pinfunction "1_1") (pintype "passive"))
      (node (ref "JP7") (pin "1") (pinfunction "1_1") (pintype "passive"))
      (node (ref "JP8") (pin "1") (pinfunction "1_1") (pintype "passive"))
      (node (ref "JP9") (pin "1") (pinfunction "1_1") (pintype "passive"))
      (node (ref "LED1") (pin "A") (pinfunction "A_A") (pintype "passive"))
      (node (ref "LED10") (pin "A") (pinfunction "A_A") (pintype "passive"))
      (node (ref "LED11") (pin "A") (pinfunction "A_A") (pintype "passive"))
      (node (ref "LED12") (pin "A") (pinfunction "A_A") (pintype "passive"))
      (node (ref "LED13") (pin "A") (pinfunction "A_A") (pintype "passive"))
      (node (ref "LED14") (pin "A") (pinfunction "A_A") (pintype "passive"))
      (node (ref "LED15") (pin "A") (pinfunction "A_A") (pintype "passive"))
      (node (ref "LED16") (pin "A") (pinfunction "A_A") (pintype "passive"))
      (node (ref "LED17") (pin "A") (pinfunction "A_A") (pintype "passive"))
      (node (ref "LED18") (pin "A") (pinfunction "A_A") (pintype "passive"))
      (node (ref "LED19") (pin "A") (pinfunction "A_A") (pintype "passive"))
      (node (ref "LED2") (pin "A") (pinfunction "A_A") (pintype "passive"))
      (node (ref "LED20") (pin "A") (pinfunction "A_A") (pintype "passive"))
      (node (ref "LED21") (pin "A") (pinfunction "A_A") (pintype "passive"))
      (node (ref "LED22") (pin "A") (pinfunction "A_A") (pintype "passive"))
      (node (ref "LED23") (pin "A") (pinfunction "A_A") (pintype "passive"))
      (node (ref "LED24") (pin "A") (pinfunction "A_A") (pintype "passive"))
      (node (ref "LED25") (pin "A") (pinfunction "A_A") (pintype "passive"))
      (node (ref "LED26") (pin "A") (pinfunction "A_A") (pintype "passive"))
      (node (ref "LED27") (pin "A") (pinfunction "A_A") (pintype "passive"))
      (node (ref "LED28") (pin "A") (pinfunction "A_A") (pintype "passive"))
      (node (ref "LED29") (pin "A") (pinfunction "A_A") (pintype "passive"))
      (node (ref "LED3") (pin "A") (pinfunction "A_A") (pintype "passive"))
      (node (ref "LED30") (pin "A") (pinfunction "A_A") (pintype "passive"))
      (node (ref "LED31") (pin "A") (pinfunction "A_A") (pintype "passive"))
      (node (ref "LED32") (pin "A") (pinfunction "A_A") (pintype "passive"))
      (node (ref "LED4") (pin "A") (pinfunction "A_A") (pintype "passive"))
      (node (ref "LED5") (pin "A") (pinfunction "A_A") (pintype "passive"))
      (node (ref "LED6") (pin "A") (pinfunction "A_A") (pintype "passive"))
      (node (ref "LED7") (pin "A") (pinfunction "A_A") (pintype "passive"))
      (node (ref "LED8") (pin "A") (pinfunction "A_A") (pintype "passive"))
      (node (ref "LED9") (pin "A") (pinfunction "A_A") (pintype "passive"))
      (node (ref "Q1") (pin "1") (pinfunction "C_1") (pintype "passive"))
      (node (ref "Q10") (pin "1") (pinfunction "C_1") (pintype "passive"))
      (node (ref "Q11") (pin "1") (pinfunction "C_1") (pintype "passive"))
      (node (ref "Q12") (pin "1") (pinfunction "C_1") (pintype "passive"))
      (node (ref "Q13") (pin "1") (pinfunction "C_1") (pintype "passive"))
      (node (ref "Q14") (pin "1") (pinfunction "C_1") (pintype "passive"))
      (node (ref "Q15") (pin "1") (pinfunction "C_1") (pintype "passive"))
      (node (ref "Q16") (pin "1") (pinfunction "C_1") (pintype "passive"))
      (node (ref "Q17") (pin "1") (pinfunction "C_1") (pintype "passive"))
      (node (ref "Q18") (pin "1") (pinfunction "C_1") (pintype "passive"))
      (node (ref "Q19") (pin "1") (pinfunction "C_1") (pintype "passive"))
      (node (ref "Q2") (pin "1") (pinfunction "C_1") (pintype "passive"))
      (node (ref "Q20") (pin "1") (pinfunction "C_1") (pintype "passive"))
      (node (ref "Q21") (pin "1") (pinfunction "C_1") (pintype "passive"))
      (node (ref "Q22") (pin "1") (pinfunction "C_1") (pintype "passive"))
      (node (ref "Q23") (pin "1") (pinfunction "C_1") (pintype "passive"))
      (node (ref "Q24") (pin "1") (pinfunction "C_1") (pintype "passive"))
      (node (ref "Q25") (pin "1") (pinfunction "C_1") (pintype "passive"))
      (node (ref "Q26") (pin "1") (pinfunction "C_1") (pintype "passive"))
      (node (ref "Q27") (pin "1") (pinfunction "C_1") (pintype "passive"))
      (node (ref "Q28") (pin "1") (pinfunction "C_1") (pintype "passive"))
      (node (ref "Q29") (pin "1") (pinfunction "C_1") (pintype "passive"))
      (node (ref "Q3") (pin "1") (pinfunction "C_1") (pintype "passive"))
      (node (ref "Q30") (pin "1") (pinfunction "C_1") (pintype "passive"))
      (node (ref "Q31") (pin "1") (pinfunction "C_1") (pintype "passive"))
      (node (ref "Q32") (pin "1") (pinfunction "C_1") (pintype "passive"))
      (node (ref "Q4") (pin "1") (pinfunction "C_1") (pintype "passive"))
      (node (ref "Q5") (pin "1") (pinfunction "C_1") (pintype "passive"))
      (node (ref "Q6") (pin "1") (pinfunction "C_1") (pintype "passive"))
      (node (ref "Q7") (pin "1") (pinfunction "C_1") (pintype "passive"))
      (node (ref "Q8") (pin "1") (pinfunction "C_1") (pintype "passive"))
      (node (ref "Q9") (pin "1") (pinfunction "C_1") (pintype "passive"))
      (node (ref "R-ENA") (pin "2") (pinfunction "2_2") (pintype "passive"))
      (node (ref "U1") (pin "2") (pinfunction "3V3_2") (pintype "power_in"))
      (node (ref "V2") (pin "3") (pinfunction "V+_3") (pintype "power_in"))
      (node (ref "X1") (pin "P$5") (pinfunction "5_P$5") (pintype "passive"))
      (node (ref "X3") (pin "P$6") (pinfunction "6_P$6") (pintype "passive"))
    )
    (net (code "2") (name "/A1") (class "Default")
      (node (ref "IC1") (pin "9") (pinfunction "C_9") (pintype "input"))
      (node (ref "IC2") (pin "9") (pinfunction "C_9") (pintype "input"))
      (node (ref "IC3") (pin "9") (pinfunction "C_9") (pintype "input"))
      (node (ref "IC4") (pin "9") (pinfunction "C_9") (pintype "input"))
      (node (ref "U1") (pin "16") (pinfunction "IO13_16") (pintype "bidirectional"))
    )
    (net (code "3") (name "/A2") (class "Default")
      (node (ref "IC1") (pin "10") (pinfunction "B_10") (pintype "input"))
      (node (ref "IC2") (pin "10") (pinfunction "B_10") (pintype "input"))
      (node (ref "IC3") (pin "10") (pinfunction "B_10") (pintype "input"))
      (node (ref "IC4") (pin "10") (pinfunction "B_10") (pintype "input"))
      (node (ref "U1") (pin "12") (pinfunction "IO27_12") (pintype "bidirectional"))
    )
    (net (code "4") (name "/A3") (class "Default")
      (node (ref "IC1") (pin "11") (pinfunction "A_11") (pintype "input"))
      (node (ref "IC2") (pin "11") (pinfunction "A_11") (pintype "input"))
      (node (ref "IC3") (pin "11") (pinfunction "A_11") (pintype "input"))
      (node (ref "IC4") (pin "11") (pinfunction "A_11") (pintype "input"))
      (node (ref "U1") (pin "13") (pinfunction "IO14_13") (pintype "bidirectional"))
    )
    (net (code "5") (name "/D1") (class "Default")
      (node (ref "IC2") (pin "3") (pinfunction "X_3") (pintype "bidirectional"))
      (node (ref "U1") (pin "8") (pinfunction "IO32_8") (pintype "bidirectional"))
    )
    (net (code "6") (name "/D2") (class "Default")
      (node (ref "IC1") (pin "3") (pinfunction "X_3") (pintype "bidirectional"))
      (node (ref "U1") (pin "9") (pinfunction "IO33_9") (pintype "bidirectional"))
    )
    (net (code "7") (name "/D3") (class "Default")
      (node (ref "IC3") (pin "3") (pinfunction "X_3") (pintype "bidirectional"))
      (node (ref "U1") (pin "10") (pinfunction "IO25_10") (pintype "bidirectional"))
    )
    (net (code "8") (name "/D4") (class "Default")
      (node (ref "IC4") (pin "3") (pinfunction "X_3") (pintype "bidirectional"))
      (node (ref "U1") (pin "11") (pinfunction "IO26_11") (pintype "bidirectional"))
    )
    (net (code "9") (name "/LED") (class "Default")
      (node (ref "LED-R1") (pin "1") (pinfunction "1_1") (pintype "passive"))
      (node (ref "LED-R10") (pin "1") (pinfunction "1_1") (pintype "passive"))
      (node (ref "LED-R11") (pin "1") (pinfunction "1_1") (pintype "passive"))
      (node (ref "LED-R12") (pin "1") (pinfunction "1_1") (pintype "passive"))
      (node (ref "LED-R13") (pin "1") (pinfunction "1_1") (pintype "passive"))
      (node (ref "LED-R14") (pin "1") (pinfunction "1_1") (pintype "passive"))
      (node (ref "LED-R15") (pin "1") (pinfunction "1_1") (pintype "passive"))
      (node (ref "LED-R16") (pin "1") (pinfunction "1_1") (pintype "passive"))
      (node (ref "LED-R17") (pin "1") (pinfunction "1_1") (pintype "passive"))
      (node (ref "LED-R18") (pin "1") (pinfunction "1_1") (pintype "passive"))
      (node (ref "LED-R19") (pin "1") (pinfunction "1_1") (pintype "passive"))
      (node (ref "LED-R2") (pin "1") (pinfunction "1_1") (pintype "passive"))
      (node (ref "LED-R20") (pin "1") (pinfunction "1_1") (pintype "passive"))
      (node (ref "LED-R21") (pin "1") (pinfunction "1_1") (pintype "passive"))
      (node (ref "LED-R22") (pin "1") (pinfunction "1_1") (pintype "passive"))
      (node (ref "LED-R23") (pin "1") (pinfunction "1_1") (pintype "passive"))
      (node (ref "LED-R24") (pin "1") (pinfunction "1_1") (pintype "passive"))
      (node (ref "LED-R25") (pin "1") (pinfunction "1_1") (pintype "passive"))
      (node (ref "LED-R26") (pin "1") (pinfunction "1_1") (pintype "passive"))
      (node (ref "LED-R27") (pin "1") (pinfunction "1_1") (pintype "passive"))
      (node (ref "LED-R28") (pin "1") (pinfunction "1_1") (pintype "passive"))
      (node (ref "LED-R29") (pin "1") (pinfunction "1_1") (pintype "passive"))
      (node (ref "LED-R3") (pin "1") (pinfunction "1_1") (pintype "passive"))
      (node (ref "LED-R30") (pin "1") (pinfunction "1_1") (pintype "passive"))
      (node (ref "LED-R31") (pin "1") (pinfunction "1_1") (pintype "passive"))
      (node (ref "LED-R32") (pin "1") (pinfunction "1_1") (pintype "passive"))
      (node (ref "LED-R4") (pin "1") (pinfunction "1_1") (pintype "passive"))
      (node (ref "LED-R5") (pin "1") (pinfunction "1_1") (pintype "passive"))
      (node (ref "LED-R6") (pin "1") (pinfunction "1_1") (pintype "passive"))
      (node (ref "LED-R7") (pin "1") (pinfunction "1_1") (pintype "passive"))
      (node (ref "LED-R8") (pin "1") (pinfunction "1_1") (pintype "passive"))
      (node (ref "LED-R9") (pin "1") (pinfunction "1_1") (pintype "passive"))
      (node (ref "V1") (pin "D") (pinfunction "D_D") (pintype "passive"))
    )
    (net (code "10") (name "GND") (class "Default")
      (node (ref "C37") (pin "2") (pinfunction "2_2") (pintype "passive"))
      (node (ref "C4") (pin "-") (pinfunction "-_-") (pintype "passive"))
      (node (ref "C5") (pin "-") (pinfunction "-_-") (pintype "passive"))
      (node (ref "IC1") (pin "6") (pinfunction "INH_6") (pintype "input"))
      (node (ref "IC2") (pin "6") (pinfunction "INH_6") (pintype "input"))
      (node (ref "IC3") (pin "6") (pinfunction "INH_6") (pintype "input"))
      (node (ref "IC4") (pin "6") (pinfunction "INH_6") (pintype "input"))
      (node (ref "JP33") (pin "1") (pinfunction "1_1") (pintype "passive"))
      (node (ref "JP34") (pin "1") (pinfunction "1_1") (pintype "passive"))
      (node (ref "JP35") (pin "1") (pinfunction "1_1") (pintype "passive"))
      (node (ref "JP36") (pin "1") (pinfunction "1_1") (pintype "passive"))
      (node (ref "JP37") (pin "1") (pinfunction "1_1") (pintype "passive"))
      (node (ref "JP38") (pin "1") (pinfunction "1_1") (pintype "passive"))
      (node (ref "JP39") (pin "1") (pinfunction "1_1") (pintype "passive"))
      (node (ref "JP40") (pin "1") (pinfunction "1_1") (pintype "passive"))
      (node (ref "JP41") (pin "1") (pinfunction "1_1") (pintype "passive"))
      (node (ref "JP42") (pin "1") (pinfunction "1_1") (pintype "passive"))
      (node (ref "JP43") (pin "1") (pinfunction "1_1") (pintype "passive"))
      (node (ref "JP44") (pin "1") (pinfunction "1_1") (pintype "passive"))
      (node (ref "JP45") (pin "1") (pinfunction "1_1") (pintype "passive"))
      (node (ref "JP46") (pin "1") (pinfunction "1_1") (pintype "passive"))
      (node (ref "JP47") (pin "1") (pinfunction "1_1") (pintype "passive"))
      (node (ref "JP48") (pin "1") (pinfunction "1_1") (pintype "passive"))
      (node (ref "JP49") (pin "1") (pinfunction "1_1") (pintype "passive"))
      (node (ref "JP50") (pin "1") (pinfunction "1_1") (pintype "passive"))
      (node (ref "JP51") (pin "1") (pinfunction "1_1") (pintype "passive"))
      (node (ref "JP52") (pin "1") (pinfunction "1_1") (pintype "passive"))
      (node (ref "JP53") (pin "1") (pinfunction "1_1") (pintype "passive"))
      (node (ref "JP54") (pin "1") (pinfunction "1_1") (pintype "passive"))
      (node (ref "JP55") (pin "1") (pinfunction "1_1") (pintype "passive"))
      (node (ref "JP56") (pin "1") (pinfunction "1_1") (pintype "passive"))
      (node (ref "JP57") (pin "1") (pinfunction "1_1") (pintype "passive"))
      (node (ref "JP58") (pin "1") (pinfunction "1_1") (pintype "passive"))
      (node (ref "JP59") (pin "1") (pinfunction "1_1") (pintype "passive"))
      (node (ref "JP60") (pin "1") (pinfunction "1_1") (pintype "passive"))
      (node (ref "JP61") (pin "1") (pinfunction "1_1") (pintype "passive"))
      (node (ref "JP62") (pin "1") (pinfunction "1_1") (pintype "passive"))
      (node (ref "JP63") (pin "1") (pinfunction "1_1") (pintype "passive"))
      (node (ref "JP64") (pin "1") (pinfunction "1_1") (pintype "passive"))
      (node (ref "R1") (pin "2") (pinfunction "2_2") (pintype "passive"))
      (node (ref "R10") (pin "2") (pinfunction "2_2") (pintype "passive"))
      (node (ref "R11") (pin "2") (pinfunction "2_2") (pintype "passive"))
      (node (ref "R12") (pin "2") (pinfunction "2_2") (pintype "passive"))
      (node (ref "R13") (pin "2") (pinfunction "2_2") (pintype "passive"))
      (node (ref "R14") (pin "2") (pinfunction "2_2") (pintype "passive"))
      (node (ref "R15") (pin "2") (pinfunction "2_2") (pintype "passive"))
      (node (ref "R16") (pin "2") (pinfunction "2_2") (pintype "passive"))
      (node (ref "R17") (pin "2") (pinfunction "2_2") (pintype "passive"))
      (node (ref "R18") (pin "2") (pinfunction "2_2") (pintype "passive"))
      (node (ref "R19") (pin "2") (pinfunction "2_2") (pintype "passive"))
      (node (ref "R2") (pin "2") (pinfunction "2_2") (pintype "passive"))
      (node (ref "R20") (pin "2") (pinfunction "2_2") (pintype "passive"))
      (node (ref "R21") (pin "2") (pinfunction "2_2") (pintype "passive"))
      (node (ref "R22") (pin "2") (pinfunction "2_2") (pintype "passive"))
      (node (ref "R23") (pin "2") (pinfunction "2_2") (pintype "passive"))
      (node (ref "R24") (pin "2") (pinfunction "2_2") (pintype "passive"))
      (node (ref "R25") (pin "2") (pinfunction "2_2") (pintype "passive"))
      (node (ref "R26") (pin "2") (pinfunction "2_2") (pintype "passive"))
      (node (ref "R27") (pin "2") (pinfunction "2_2") (pintype "passive"))
      (node (ref "R28") (pin "2") (pinfunction "2_2") (pintype "passive"))
      (node (ref "R29") (pin "2") (pinfunction "2_2") (pintype "passive"))
      (node (ref "R3") (pin "2") (pinfunction "2_2") (pintype "passive"))
      (node (ref "R30") (pin "2") (pinfunction "2_2") (pintype "passive"))
      (node (ref "R31") (pin "2") (pinfunction "2_2") (pintype "passive"))
      (node (ref "R32") (pin "2") (pinfunction "2_2") (pintype "passive"))
      (node (ref "R4") (pin "2") (pinfunction "2_2") (pintype "passive"))
      (node (ref "R5") (pin "2") (pinfunction "2_2") (pintype "passive"))
      (node (ref "R6") (pin "2") (pinfunction "2_2") (pintype "passive"))
      (node (ref "R7") (pin "2") (pinfunction "2_2") (pintype "passive"))
      (node (ref "R8") (pin "2") (pinfunction "2_2") (pintype "passive"))
      (node (ref "R9") (pin "2") (pinfunction "2_2") (pintype "passive"))
      (node (ref "U1") (pin "1") (pinfunction "GND_1") (pintype "power_in"))
      (node (ref "U1") (pin "15") (pinfunction "GND_15") (pintype "power_in"))
      (node (ref "U1") (pin "38") (pinfunction "GND_38") (pintype "power_in"))
      (node (ref "U1") (pin "GND") (pinfunction "GND_GND") (pintype "power_in"))
      (node (ref "V1") (pin "S") (pinfunction "S_S") (pintype "passive"))
      (node (ref "V2") (pin "2") (pinfunction "GND_2") (pintype "power_in"))
      (node (ref "V2") (pin "5") (pinfunction "LBK_5") (pintype "input"))
      (node (ref "V2") (pin "8") (pinfunction "RS_8") (pintype "input"))
      (node (ref "X1") (pin "P$1") (pinfunction "1_P$1") (pintype "passive"))
      (node (ref "X1") (pin "P$2") (pinfunction "2_P$2") (pintype "passive"))
      (node (ref "X3") (pin "P$1") (pinfunction "1_P$1") (pintype "passive"))
    )
    (net (code "11") (name "Net-(IC1A-X0)") (class "Default")
      (node (ref "IC1") (pin "13") (pinfunction "X0_13") (pintype "bidirectional"))
      (node (ref "Q6") (pin "2") (pinfunction "E_2") (pintype "passive"))
      (node (ref "R6") (pin "1") (pinfunction "1_1") (pintype "passive"))
    )
    (net (code "12") (name "Net-(IC1A-X1)") (class "Default")
      (node (ref "IC1") (pin "14") (pinfunction "X1_14") (pintype "bidirectional"))
      (node (ref "Q7") (pin "2") (pinfunction "E_2") (pintype "passive"))
      (node (ref "R7") (pin "1") (pinfunction "1_1") (pintype "passive"))
    )
    (net (code "13") (name "Net-(IC1A-X2)") (class "Default")
      (node (ref "IC1") (pin "15") (pinfunction "X2_15") (pintype "bidirectional"))
      (node (ref "Q8") (pin "2") (pinfunction "E_2") (pintype "passive"))
      (node (ref "R8") (pin "1") (pinfunction "1_1") (pintype "passive"))
    )
    (net (code "14") (name "Net-(IC1A-X3)") (class "Default")
      (node (ref "IC1") (pin "12") (pinfunction "X3_12") (pintype "bidirectional"))
      (node (ref "Q5") (pin "2") (pinfunction "E_2") (pintype "passive"))
      (node (ref "R5") (pin "1") (pinfunction "1_1") (pintype "passive"))
    )
    (net (code "15") (name "Net-(IC1A-X4)") (class "Default")
      (node (ref "IC1") (pin "1") (pinfunction "X4_1") (pintype "bidirectional"))
      (node (ref "Q1") (pin "2") (pinfunction "E_2") (pintype "passive"))
      (node (ref "R1") (pin "1") (pinfunction "1_1") (pintype "passive"))
    )
    (net (code "16") (name "Net-(IC1A-X5)") (class "Default")
      (node (ref "IC1") (pin "5") (pinfunction "X5_5") (pintype "bidirectional"))
      (node (ref "Q4") (pin "2") (pinfunction "E_2") (pintype "passive"))
      (node (ref "R4") (pin "1") (pinfunction "1_1") (pintype "passive"))
    )
    (net (code "17") (name "Net-(IC1A-X6)") (class "Default")
      (node (ref "IC1") (pin "2") (pinfunction "X6_2") (pintype "bidirectional"))
      (node (ref "Q2") (pin "2") (pinfunction "E_2") (pintype "passive"))
      (node (ref "R2") (pin "1") (pinfunction "1_1") (pintype "passive"))
    )
    (net (code "18") (name "Net-(IC1A-X7)") (class "Default")
      (node (ref "IC1") (pin "4") (pinfunction "X7_4") (pintype "bidirectional"))
      (node (ref "Q3") (pin "2") (pinfunction "E_2") (pintype "passive"))
      (node (ref "R3") (pin "1") (pinfunction "1_1") (pintype "passive"))
    )
    (net (code "19") (name "Net-(IC2A-X0)") (class "Default")
      (node (ref "IC2") (pin "13") (pinfunction "X0_13") (pintype "bidirectional"))
      (node (ref "Q14") (pin "2") (pinfunction "E_2") (pintype "passive"))
      (node (ref "R14") (pin "1") (pinfunction "1_1") (pintype "passive"))
    )
    (net (code "20") (name "Net-(IC2A-X1)") (class "Default")
      (node (ref "IC2") (pin "14") (pinfunction "X1_14") (pintype "bidirectional"))
      (node (ref "Q15") (pin "2") (pinfunction "E_2") (pintype "passive"))
      (node (ref "R15") (pin "1") (pinfunction "1_1") (pintype "passive"))
    )
    (net (code "21") (name "Net-(IC2A-X2)") (class "Default")
      (node (ref "IC2") (pin "15") (pinfunction "X2_15") (pintype "bidirectional"))
      (node (ref "Q16") (pin "2") (pinfunction "E_2") (pintype "passive"))
      (node (ref "R16") (pin "1") (pinfunction "1_1") (pintype "passive"))
    )
    (net (code "22") (name "Net-(IC2A-X3)") (class "Default")
      (node (ref "IC2") (pin "12") (pinfunction "X3_12") (pintype "bidirectional"))
      (node (ref "Q13") (pin "2") (pinfunction "E_2") (pintype "passive"))
      (node (ref "R13") (pin "1") (pinfunction "1_1") (pintype "passive"))
    )
    (net (code "23") (name "Net-(IC2A-X4)") (class "Default")
      (node (ref "IC2") (pin "1") (pinfunction "X4_1") (pintype "bidirectional"))
      (node (ref "Q9") (pin "2") (pinfunction "E_2") (pintype "passive"))
      (node (ref "R9") (pin "1") (pinfunction "1_1") (pintype "passive"))
    )
    (net (code "24") (name "Net-(IC2A-X5)") (class "Default")
      (node (ref "IC2") (pin "5") (pinfunction "X5_5") (pintype "bidirectional"))
      (node (ref "Q12") (pin "2") (pinfunction "E_2") (pintype "passive"))
      (node (ref "R12") (pin "1") (pinfunction "1_1") (pintype "passive"))
    )
    (net (code "25") (name "Net-(IC2A-X6)") (class "Default")
      (node (ref "IC2") (pin "2") (pinfunction "X6_2") (pintype "bidirectional"))
      (node (ref "Q10") (pin "2") (pinfunction "E_2") (pintype "passive"))
      (node (ref "R10") (pin "1") (pinfunction "1_1") (pintype "passive"))
    )
    (net (code "26") (name "Net-(IC2A-X7)") (class "Default")
      (node (ref "IC2") (pin "4") (pinfunction "X7_4") (pintype "bidirectional"))
      (node (ref "Q11") (pin "2") (pinfunction "E_2") (pintype "passive"))
      (node (ref "R11") (pin "1") (pinfunction "1_1") (pintype "passive"))
    )
    (net (code "27") (name "Net-(IC3A-X0)") (class "Default")
      (node (ref "IC3") (pin "13") (pinfunction "X0_13") (pintype "bidirectional"))
      (node (ref "Q22") (pin "2") (pinfunction "E_2") (pintype "passive"))
      (node (ref "R22") (pin "1") (pinfunction "1_1") (pintype "passive"))
    )
    (net (code "28") (name "Net-(IC3A-X1)") (class "Default")
      (node (ref "IC3") (pin "14") (pinfunction "X1_14") (pintype "bidirectional"))
      (node (ref "Q23") (pin "2") (pinfunction "E_2") (pintype "passive"))
      (node (ref "R23") (pin "1") (pinfunction "1_1") (pintype "passive"))
    )
    (net (code "29") (name "Net-(IC3A-X2)") (class "Default")
      (node (ref "IC3") (pin "15") (pinfunction "X2_15") (pintype "bidirectional"))
      (node (ref "Q24") (pin "2") (pinfunction "E_2") (pintype "passive"))
      (node (ref "R24") (pin "1") (pinfunction "1_1") (pintype "passive"))
    )
    (net (code "30") (name "Net-(IC3A-X3)") (class "Default")
      (node (ref "IC3") (pin "12") (pinfunction "X3_12") (pintype "bidirectional"))
      (node (ref "Q21") (pin "2") (pinfunction "E_2") (pintype "passive"))
      (node (ref "R21") (pin "1") (pinfunction "1_1") (pintype "passive"))
    )
    (net (code "31") (name "Net-(IC3A-X4)") (class "Default")
      (node (ref "IC3") (pin "1") (pinfunction "X4_1") (pintype "bidirectional"))
      (node (ref "Q17") (pin "2") (pinfunction "E_2") (pintype "passive"))
      (node (ref "R17") (pin "1") (pinfunction "1_1") (pintype "passive"))
    )
    (net (code "32") (name "Net-(IC3A-X5)") (class "Default")
      (node (ref "IC3") (pin "5") (pinfunction "X5_5") (pintype "bidirectional"))
      (node (ref "Q20") (pin "2") (pinfunction "E_2") (pintype "passive"))
      (node (ref "R20") (pin "1") (pinfunction "1_1") (pintype "passive"))
    )
    (net (code "33") (name "Net-(IC3A-X6)") (class "Default")
      (node (ref "IC3") (pin "2") (pinfunction "X6_2") (pintype "bidirectional"))
      (node (ref "Q18") (pin "2") (pinfunction "E_2") (pintype "passive"))
      (node (ref "R18") (pin "1") (pinfunction "1_1") (pintype "passive"))
    )
    (net (code "34") (name "Net-(IC3A-X7)") (class "Default")
      (node (ref "IC3") (pin "4") (pinfunction "X7_4") (pintype "bidirectional"))
      (node (ref "Q19") (pin "2") (pinfunction "E_2") (pintype "passive"))
      (node (ref "R19") (pin "1") (pinfunction "1_1") (pintype "passive"))
    )
    (net (code "35") (name "Net-(IC4A-X0)") (class "Default")
      (node (ref "IC4") (pin "13") (pinfunction "X0_13") (pintype "bidirectional"))
      (node (ref "Q30") (pin "2") (pinfunction "E_2") (pintype "passive"))
      (node (ref "R30") (pin "1") (pinfunction "1_1") (pintype "passive"))
    )
    (net (code "36") (name "Net-(IC4A-X1)") (class "Default")
      (node (ref "IC4") (pin "14") (pinfunction "X1_14") (pintype "bidirectional"))
      (node (ref "Q31") (pin "2") (pinfunction "E_2") (pintype "passive"))
      (node (ref "R31") (pin "1") (pinfunction "1_1") (pintype "passive"))
    )
    (net (code "37") (name "Net-(IC4A-X2)") (class "Default")
      (node (ref "IC4") (pin "15") (pinfunction "X2_15") (pintype "bidirectional"))
      (node (ref "Q32") (pin "2") (pinfunction "E_2") (pintype "passive"))
      (node (ref "R32") (pin "1") (pinfunction "1_1") (pintype "passive"))
    )
    (net (code "38") (name "Net-(IC4A-X3)") (class "Default")
      (node (ref "IC4") (pin "12") (pinfunction "X3_12") (pintype "bidirectional"))
      (node (ref "Q29") (pin "2") (pinfunction "E_2") (pintype "passive"))
      (node (ref "R29") (pin "1") (pinfunction "1_1") (pintype "passive"))
    )
    (net (code "39") (name "Net-(IC4A-X4)") (class "Default")
      (node (ref "IC4") (pin "1") (pinfunction "X4_1") (pintype "bidirectional"))
      (node (ref "Q25") (pin "2") (pinfunction "E_2") (pintype "passive"))
      (node (ref "R25") (pin "1") (pinfunction "1_1") (pintype "passive"))
    )
    (net (code "40") (name "Net-(IC4A-X5)") (class "Default")
      (node (ref "IC4") (pin "5") (pinfunction "X5_5") (pintype "bidirectional"))
      (node (ref "Q28") (pin "2") (pinfunction "E_2") (pintype "passive"))
      (node (ref "R28") (pin "1") (pinfunction "1_1") (pintype "passive"))
    )
    (net (code "41") (name "Net-(IC4A-X6)") (class "Default")
      (node (ref "IC4") (pin "2") (pinfunction "X6_2") (pintype "bidirectional"))
      (node (ref "Q26") (pin "2") (pinfunction "E_2") (pintype "passive"))
      (node (ref "R26") (pin "1") (pinfunction "1_1") (pintype "passive"))
    )
    (net (code "42") (name "Net-(IC4A-X7)") (class "Default")
      (node (ref "IC4") (pin "4") (pinfunction "X7_4") (pintype "bidirectional"))
      (node (ref "Q27") (pin "2") (pinfunction "E_2") (pintype "passive"))
      (node (ref "R27") (pin "1") (pinfunction "1_1") (pintype "passive"))
    )
    (net (code "43") (name "Net-(LED-R1-Pad2)") (class "Default")
      (node (ref "LED-R1") (pin "2") (pinfunction "2_2") (pintype "passive"))
      (node (ref "LED1") (pin "C") (pinfunction "C_C") (pintype "passive"))
    )
    (net (code "44") (name "Net-(LED-R2-Pad2)") (class "Default")
      (node (ref "LED-R2") (pin "2") (pinfunction "2_2") (pintype "passive"))
      (node (ref "LED2") (pin "C") (pinfunction "C_C") (pintype "passive"))
    )
    (net (code "45") (name "Net-(LED-R3-Pad2)") (class "Default")
      (node (ref "LED-R3") (pin "2") (pinfunction "2_2") (pintype "passive"))
      (node (ref "LED3") (pin "C") (pinfunction "C_C") (pintype "passive"))
    )
    (net (code "46") (name "Net-(LED-R4-Pad2)") (class "Default")
      (node (ref "LED-R4") (pin "2") (pinfunction "2_2") (pintype "passive"))
      (node (ref "LED4") (pin "C") (pinfunction "C_C") (pintype "passive"))
    )
    (net (code "47") (name "Net-(LED-R5-Pad2)") (class "Default")
      (node (ref "LED-R5") (pin "2") (pinfunction "2_2") (pintype "passive"))
      (node (ref "LED5") (pin "C") (pinfunction "C_C") (pintype "passive"))
    )
    (net (code "48") (name "Net-(LED-R6-Pad2)") (class "Default")
      (node (ref "LED-R6") (pin "2") (pinfunction "2_2") (pintype "passive"))
      (node (ref "LED6") (pin "C") (pinfunction "C_C") (pintype "passive"))
    )
    (net (code "49") (name "Net-(LED-R7-Pad2)") (class "Default")
      (node (ref "LED-R7") (pin "2") (pinfunction "2_2") (pintype "passive"))
      (node (ref "LED7") (pin "C") (pinfunction "C_C") (pintype "passive"))
    )
    (net (code "50") (name "Net-(LED-R8-Pad2)") (class "Default")
      (node (ref "LED-R8") (pin "2") (pinfunction "2_2") (pintype "passive"))
      (node (ref "LED8") (pin "C") (pinfunction "C_C") (pintype "passive"))
    )
    (net (code "51") (name "Net-(LED-R9-Pad2)") (class "Default")
      (node (ref "LED-R9") (pin "2") (pinfunction "2_2") (pintype "passive"))
      (node (ref "LED9") (pin "C") (pinfunction "C_C") (pintype "passive"))
    )
    (net (code "52") (name "Net-(LED-R10-Pad2)") (class "Default")
      (node (ref "LED-R10") (pin "2") (pinfunction "2_2") (pintype "passive"))
      (node (ref "LED10") (pin "C") (pinfunction "C_C") (pintype "passive"))
    )
    (net (code "53") (name "Net-(LED-R11-Pad2)") (class "Default")
      (node (ref "LED-R11") (pin "2") (pinfunction "2_2") (pintype "passive"))
      (node (ref "LED11") (pin "C") (pinfunction "C_C") (pintype "passive"))
    )
    (net (code "54") (name "Net-(LED-R12-Pad2)") (class "Default")
      (node (ref "LED-R12") (pin "2") (pinfunction "2_2") (pintype "passive"))
      (node (ref "LED12") (pin "C") (pinfunction "C_C") (pintype "passive"))
    )
    (net (code "55") (name "Net-(LED-R13-Pad2)") (class "Default")
      (node (ref "LED-R13") (pin "2") (pinfunction "2_2") (pintype "passive"))
      (node (ref "LED13") (pin "C") (pinfunction "C_C") (pintype "passive"))
    )
    (net (code "56") (name "Net-(LED-R14-Pad2)") (class "Default")
      (node (ref "LED-R14") (pin "2") (pinfunction "2_2") (pintype "passive"))
      (node (ref "LED14") (pin "C") (pinfunction "C_C") (pintype "passive"))
    )
    (net (code "57") (name "Net-(LED-R15-Pad2)") (class "Default")
      (node (ref "LED-R15") (pin "2") (pinfunction "2_2") (pintype "passive"))
      (node (ref "LED15") (pin "C") (pinfunction "C_C") (pintype "passive"))
    )
    (net (code "58") (name "Net-(LED-R16-Pad2)") (class "Default")
      (node (ref "LED-R16") (pin "2") (pinfunction "2_2") (pintype "passive"))
      (node (ref "LED16") (pin "C") (pinfunction "C_C") (pintype "passive"))
    )
    (net (code "59") (name "Net-(LED-R17-Pad2)") (class "Default")
      (node (ref "LED-R17") (pin "2") (pinfunction "2_2") (pintype "passive"))
      (node (ref "LED17") (pin "C") (pinfunction "C_C") (pintype "passive"))
    )
    (net (code "60") (name "Net-(LED-R18-Pad2)") (class "Default")
      (node (ref "LED-R18") (pin "2") (pinfunction "2_2") (pintype "passive"))
      (node (ref "LED18") (pin "C") (pinfunction "C_C") (pintype "passive"))
    )
    (net (code "61") (name "Net-(LED-R19-Pad2)") (class "Default")
      (node (ref "LED-R19") (pin "2") (pinfunction "2_2") (pintype "passive"))
      (node (ref "LED19") (pin "C") (pinfunction "C_C") (pintype "passive"))
    )
    (net (code "62") (name "Net-(LED-R20-Pad2)") (class "Default")
      (node (ref "LED-R20") (pin "2") (pinfunction "2_2") (pintype "passive"))
      (node (ref "LED20") (pin "C") (pinfunction "C_C") (pintype "passive"))
    )
    (net (code "63") (name "Net-(LED-R21-Pad2)") (class "Default")
      (node (ref "LED-R21") (pin "2") (pinfunction "2_2") (pintype "passive"))
      (node (ref "LED21") (pin "C") (pinfunction "C_C") (pintype "passive"))
    )
    (net (code "64") (name "Net-(LED-R22-Pad2)") (class "Default")
      (node (ref "LED-R22") (pin "2") (pinfunction "2_2") (pintype "passive"))
      (node (ref "LED22") (pin "C") (pinfunction "C_C") (pintype "passive"))
    )
    (net (code "65") (name "Net-(LED-R23-Pad2)") (class "Default")
      (node (ref "LED-R23") (pin "2") (pinfunction "2_2") (pintype "passive"))
      (node (ref "LED23") (pin "C") (pinfunction "C_C") (pintype "passive"))
    )
    (net (code "66") (name "Net-(LED-R24-Pad2)") (class "Default")
      (node (ref "LED-R24") (pin "2") (pinfunction "2_2") (pintype "passive"))
      (node (ref "LED24") (pin "C") (pinfunction "C_C") (pintype "passive"))
    )
    (net (code "67") (name "Net-(LED-R25-Pad2)") (class "Default")
      (node (ref "LED-R25") (pin "2") (pinfunction "2_2") (pintype "passive"))
      (node (ref "LED25") (pin "C") (pinfunction "C_C") (pintype "passive"))
    )
    (net (code "68") (name "Net-(LED-R26-Pad2)") (class "Default")
      (node (ref "LED-R26") (pin "2") (pinfunction "2_2") (pintype "passive"))
      (node (ref "LED26") (pin "C") (pinfunction "C_C") (pintype "passive"))
    )
    (net (code "69") (name "Net-(LED-R27-Pad2)") (class "Default")
      (node (ref "LED-R27") (pin "2") (pinfunction "2_2") (pintype "passive"))
      (node (ref "LED27") (pin "C") (pinfunction "C_C") (pintype "passive"))
    )
    (net (code "70") (name "Net-(LED-R28-Pad2)") (class "Default")
      (node (ref "LED-R28") (pin "2") (pinfunction "2_2") (pintype "passive"))
      (node (ref "LED28") (pin "C") (pinfunction "C_C") (pintype "passive"))
    )
    (net (code "71") (name "Net-(LED-R29-Pad2)") (class "Default")
      (node (ref "LED-R29") (pin "2") (pinfunction "2_2") (pintype "passive"))
      (node (ref "LED29") (pin "C") (pinfunction "C_C") (pintype "passive"))
    )
    (net (code "72") (name "Net-(LED-R30-Pad2)") (class "Default")
      (node (ref "LED-R30") (pin "2") (pinfunction "2_2") (pintype "passive"))
      (node (ref "LED30") (pin "C") (pinfunction "C_C") (pintype "passive"))
    )
    (net (code "73") (name "Net-(LED-R31-Pad2)") (class "Default")
      (node (ref "LED-R31") (pin "2") (pinfunction "2_2") (pintype "passive"))
      (node (ref "LED31") (pin "C") (pinfunction "C_C") (pintype "passive"))
    )
    (net (code "74") (name "Net-(LED-R32-Pad2)") (class "Default")
      (node (ref "LED-R32") (pin "2") (pinfunction "2_2") (pintype "passive"))
      (node (ref "LED32") (pin "C") (pinfunction "C_C") (pintype "passive"))
    )
    (net (code "75") (name "Net-(R-GATE-Pad1)") (class "Default")
      (node (ref "R-GATE") (pin "1") (pinfunction "1_1") (pintype "passive"))
      (node (ref "V1") (pin "G") (pinfunction "G_G") (pintype "passive"))
    )
    (net (code "76") (name "Net-(U1-EN)") (class "Default")
      (node (ref "R-ENA") (pin "1") (pinfunction "1_1") (pintype "passive"))
      (node (ref "U1") (pin "3") (pinfunction "EN_3") (pintype "input"))
      (node (ref "X3") (pin "P$2") (pinfunction "2_P$2") (pintype "passive"))
    )
    (net (code "77") (name "Net-(U1-IO0)") (class "Default")
      (node (ref "U1") (pin "25") (pinfunction "IO0_25") (pintype "bidirectional"))
      (node (ref "X3") (pin "P$3") (pinfunction "3_P$3") (pintype "passive"))
    )
    (net (code "78") (name "Net-(U1-IO2)") (class "Default")
      (node (ref "R-GATE") (pin "2") (pinfunction "2_2") (pintype "passive"))
      (node (ref "U1") (pin "24") (pinfunction "IO2_24") (pintype "bidirectional"))
    )
    (net (code "79") (name "Net-(U1-IO4)") (class "Default")
      (node (ref "U1") (pin "26") (pinfunction "IO4_26") (pintype "bidirectional"))
      (node (ref "V2") (pin "4") (pinfunction "R_4") (pintype "input"))
    )
    (net (code "80") (name "Net-(U1-IO5)") (class "Default")
      (node (ref "U1") (pin "29") (pinfunction "IO5_29") (pintype "bidirectional"))
      (node (ref "V2") (pin "1") (pinfunction "D_1") (pintype "input"))
    )
    (net (code "81") (name "Net-(U1-RXD0)") (class "Default")
      (node (ref "U1") (pin "34") (pinfunction "RXD0_34") (pintype "bidirectional"))
      (node (ref "X3") (pin "P$4") (pinfunction "4_P$4") (pintype "passive"))
    )
    (net (code "82") (name "Net-(U1-TXD0)") (class "Default")
      (node (ref "U1") (pin "35") (pinfunction "TXD0_35") (pintype "bidirectional"))
      (node (ref "X3") (pin "P$5") (pinfunction "5_P$5") (pintype "passive"))
    )
    (net (code "83") (name "Net-(V2-CANH)") (class "Default")
      (node (ref "CANTERM") (pin "2") (pinfunction "2_2") (pintype "passive"))
      (node (ref "V2") (pin "7") (pinfunction "CANH_7") (pintype "output"))
      (node (ref "X1") (pin "P$4") (pinfunction "4_P$4") (pintype "passive"))
    )
    (net (code "84") (name "Net-(V2-CANL)") (class "Default")
      (node (ref "CANTERM") (pin "1") (pinfunction "1_1") (pintype "passive"))
      (node (ref "V2") (pin "6") (pinfunction "CANL_6") (pintype "output"))
      (node (ref "X1") (pin "P$3") (pinfunction "3_P$3") (pintype "passive"))
    )
    (net (code "89") (name "unconnected-(U1-CLK-Pad20)") (class "Default")
      (node (ref "U1") (pin "20") (pinfunction "CLK_20") (pintype "bidirectional"))
    )
    (net (code "90") (name "unconnected-(U1-CMD-Pad19)") (class "Default")
      (node (ref "U1") (pin "19") (pinfunction "CMD_19") (pintype "bidirectional"))
    )
    (net (code "91") (name "unconnected-(U1-IO12-Pad14)") (class "Default")
      (node (ref "U1") (pin "14") (pinfunction "IO12_14") (pintype "bidirectional"))
    )
    (net (code "92") (name "unconnected-(U1-IO15-Pad23)") (class "Default")
      (node (ref "U1") (pin "23") (pinfunction "IO15_23") (pintype "bidirectional"))
    )
    (net (code "93") (name "unconnected-(U1-IO16-Pad27)") (class "Default")
      (node (ref "U1") (pin "27") (pinfunction "IO16_27") (pintype "bidirectional"))
    )
    (net (code "94") (name "unconnected-(U1-IO17-Pad28)") (class "Default")
      (node (ref "U1") (pin "28") (pinfunction "IO17_28") (pintype "bidirectional"))
    )
    (net (code "95") (name "unconnected-(U1-IO18-Pad30)") (class "Default")
      (node (ref "U1") (pin "30") (pinfunction "IO18_30") (pintype "bidirectional"))
    )
    (net (code "96") (name "unconnected-(U1-IO19-Pad31)") (class "Default")
      (node (ref "U1") (pin "31") (pinfunction "IO19_31") (pintype "bidirectional"))
    )
    (net (code "97") (name "unconnected-(U1-IO21-Pad33)") (class "Default")
      (node (ref "U1") (pin "33") (pinfunction "IO21_33") (pintype "bidirectional"))
    )
    (net (code "98") (name "unconnected-(U1-IO22-Pad36)") (class "Default")
      (node (ref "U1") (pin "36") (pinfunction "IO22_36") (pintype "bidirectional"))
    )
    (net (code "99") (name "unconnected-(U1-IO23-Pad37)") (class "Default")
      (node (ref "U1") (pin "37") (pinfunction "IO23_37") (pintype "bidirectional"))
    )
    (net (code "100") (name "unconnected-(U1-IO34-Pad6)") (class "Default")
      (node (ref "U1") (pin "6") (pinfunction "IO34_6") (pintype "bidirectional"))
    )
    (net (code "101") (name "unconnected-(U1-IO35-Pad7)") (class "Default")
      (node (ref "U1") (pin "7") (pinfunction "IO35_7") (pintype "bidirectional"))
    )
    (net (code "102") (name "unconnected-(U1-SD0-Pad21)") (class "Default")
      (node (ref "U1") (pin "21") (pinfunction "SD0_21") (pintype "bidirectional"))
    )
    (net (code "103") (name "unconnected-(U1-SD1-Pad22)") (class "Default")
      (node (ref "U1") (pin "22") (pinfunction "SD1_22") (pintype "bidirectional"))
    )
    (net (code "104") (name "unconnected-(U1-SD2-Pad17)") (class "Default")
      (node (ref "U1") (pin "17") (pinfunction "SD2_17") (pintype "bidirectional"))
    )
    (net (code "105") (name "unconnected-(U1-SD3-Pad18)") (class "Default")
      (node (ref "U1") (pin "18") (pinfunction "SD3_18") (pintype "bidirectional"))
    )
    (net (code "106") (name "unconnected-(U1-SENSOR_VN-Pad5)") (class "Default")
      (node (ref "U1") (pin "5") (pinfunction "SENSOR_VN_5") (pintype "bidirectional"))
    )
    (net (code "107") (name "unconnected-(U1-SENSOR_VP-Pad4)") (class "Default")
      (node (ref "U1") (pin "4") (pinfunction "SENSOR_VP_4") (pintype "bidirectional"))
    )
    (net (code "108") (name "unconnected-(X1-6-PadP$6)") (class "Default")
      (node (ref "X1") (pin "P$6") (pinfunction "6_P$6") (pintype "passive"))
    )
  )
)
